# nexus5.net
KiCad netlist of a schematic drawn in Altium Designer
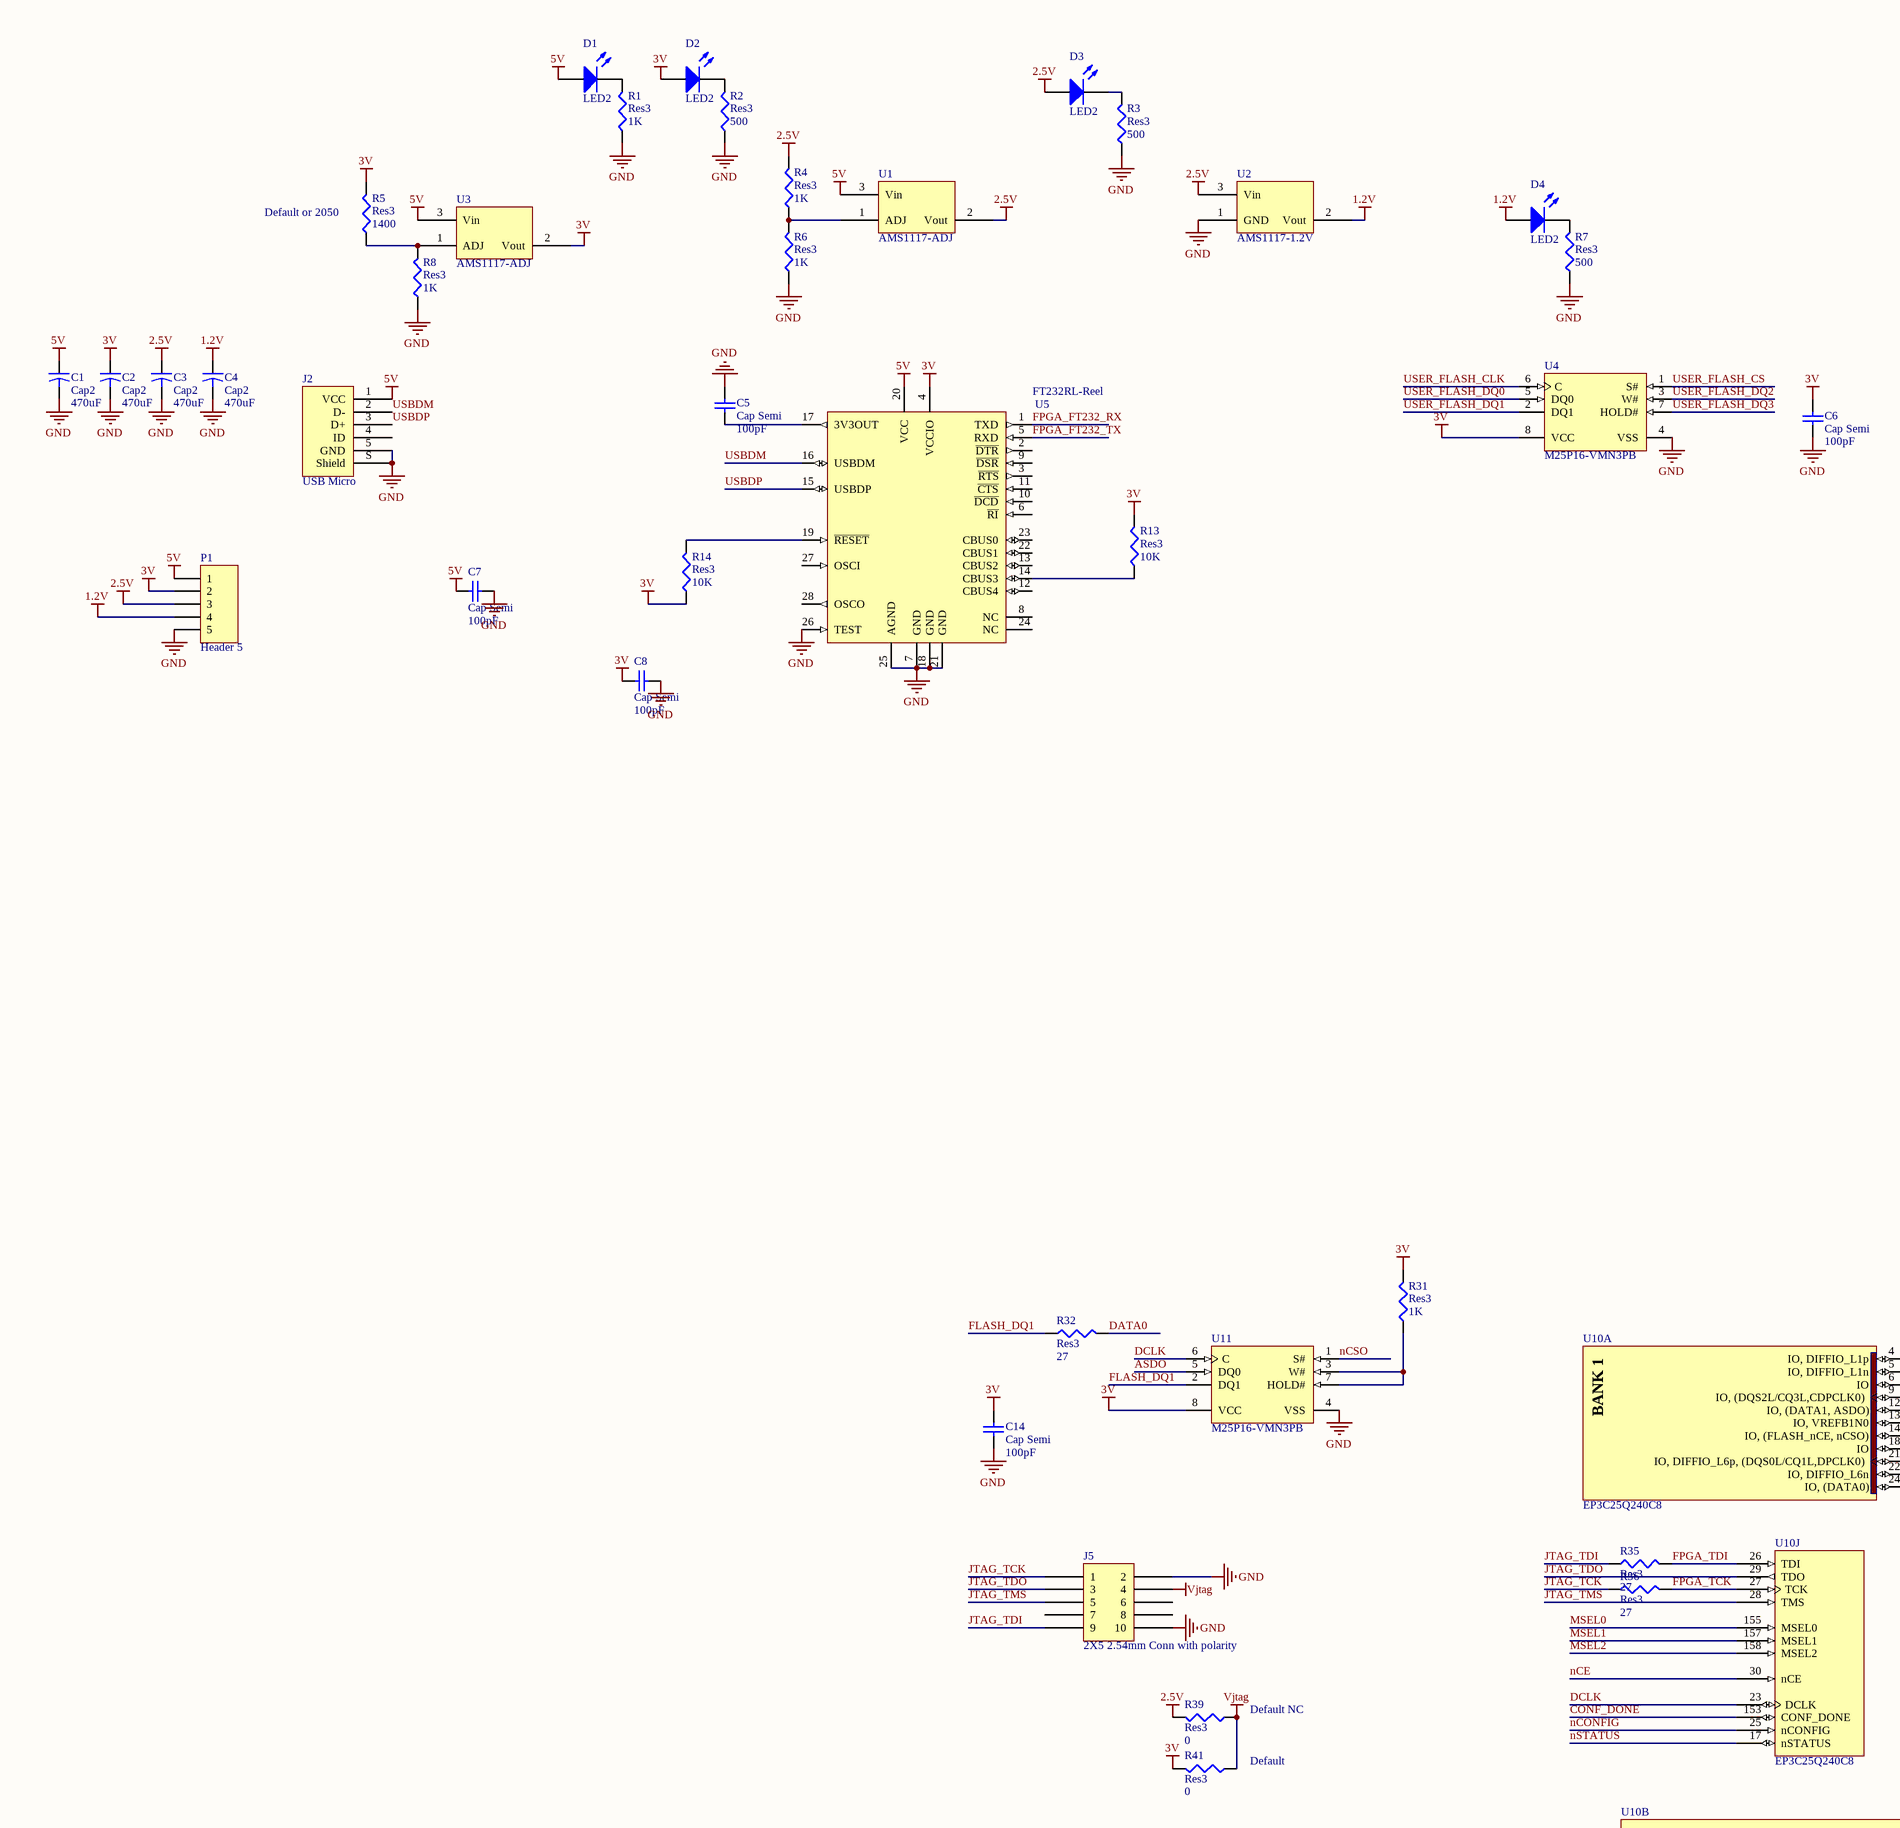
[diagram p0: nexus5.SchDoc, top left]
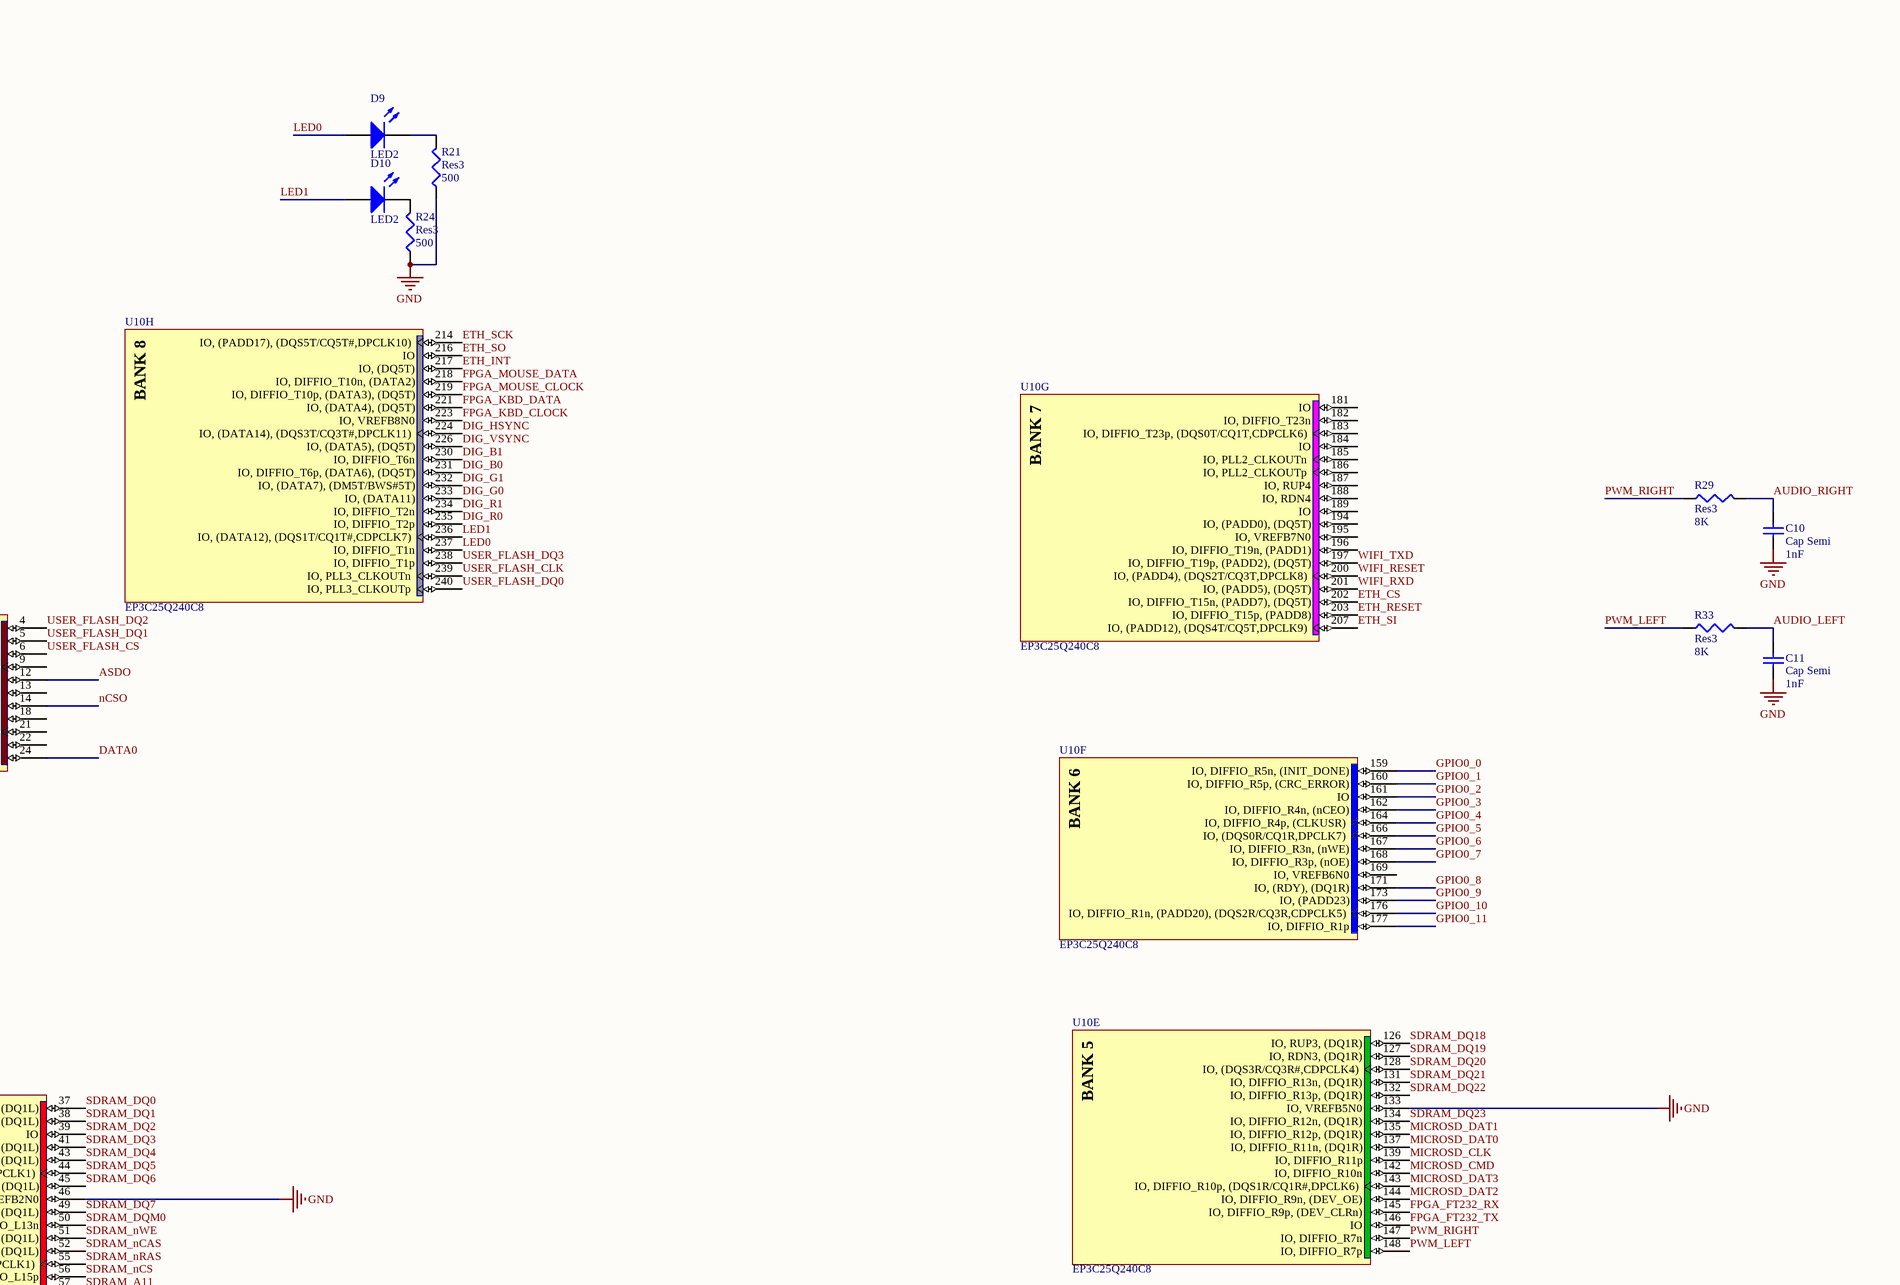
[diagram p1: nexus5.SchDoc, top middle]
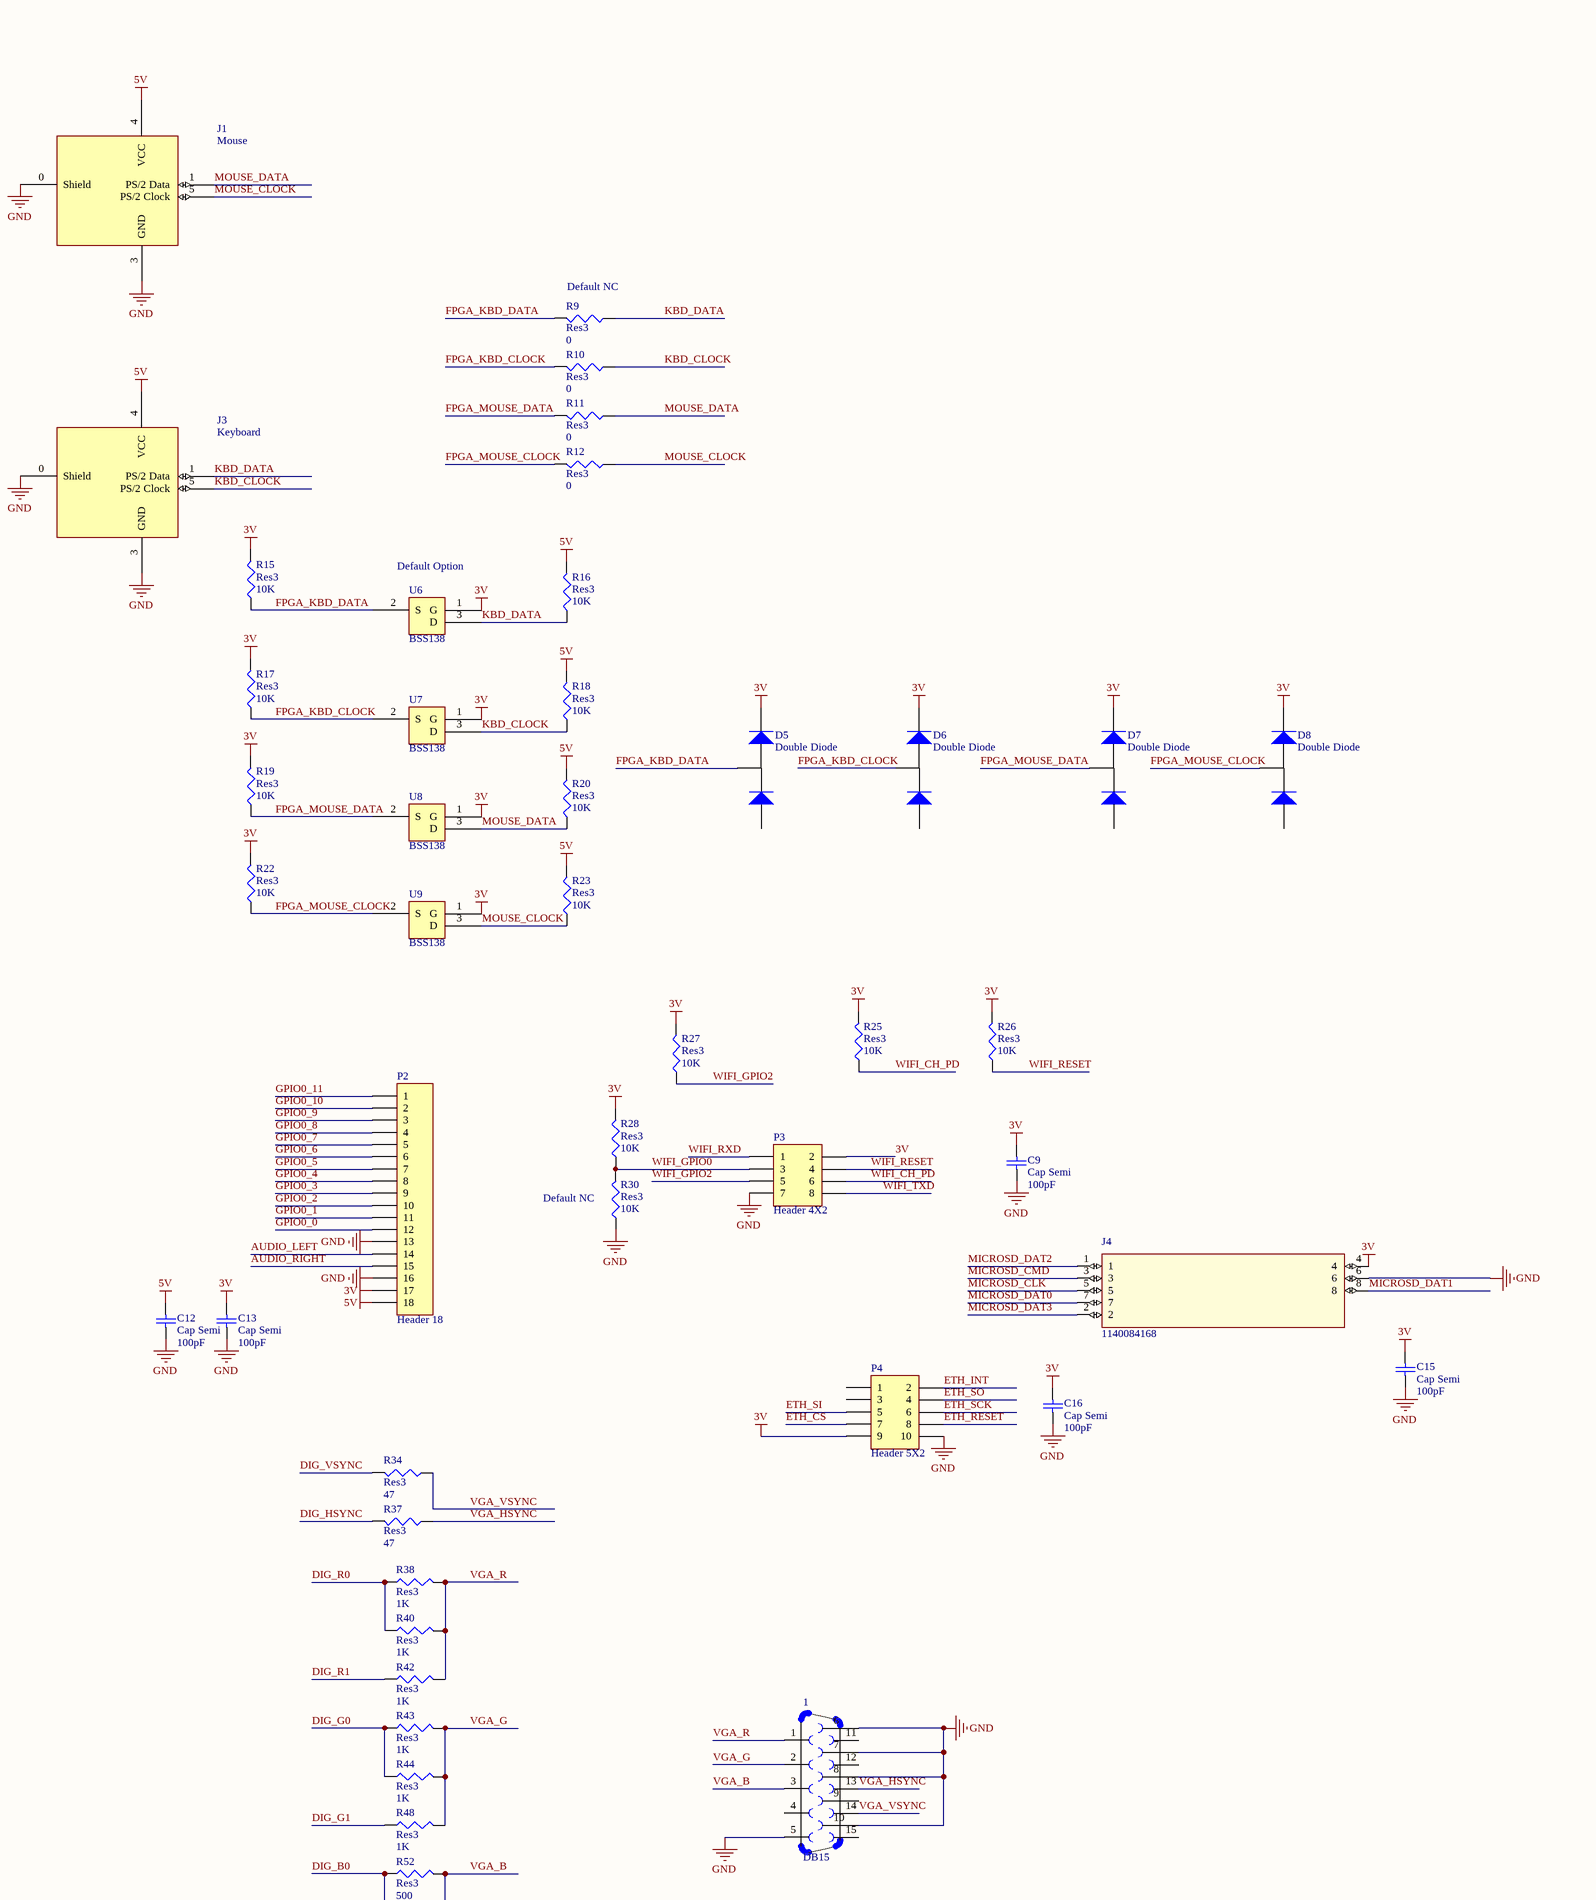
[diagram p2: nexus5.SchDoc, top right]
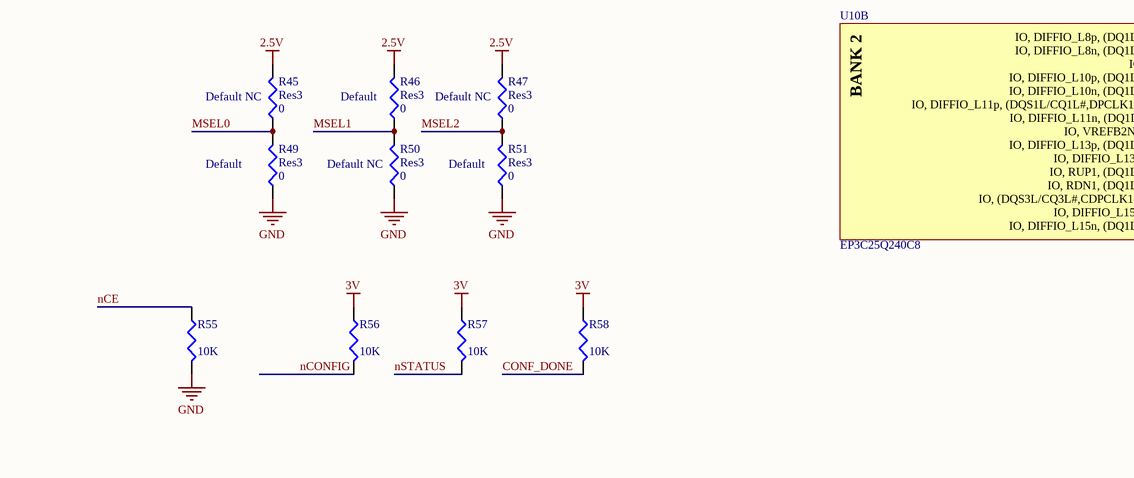
[diagram p3: nexus5.SchDoc, bottom left]
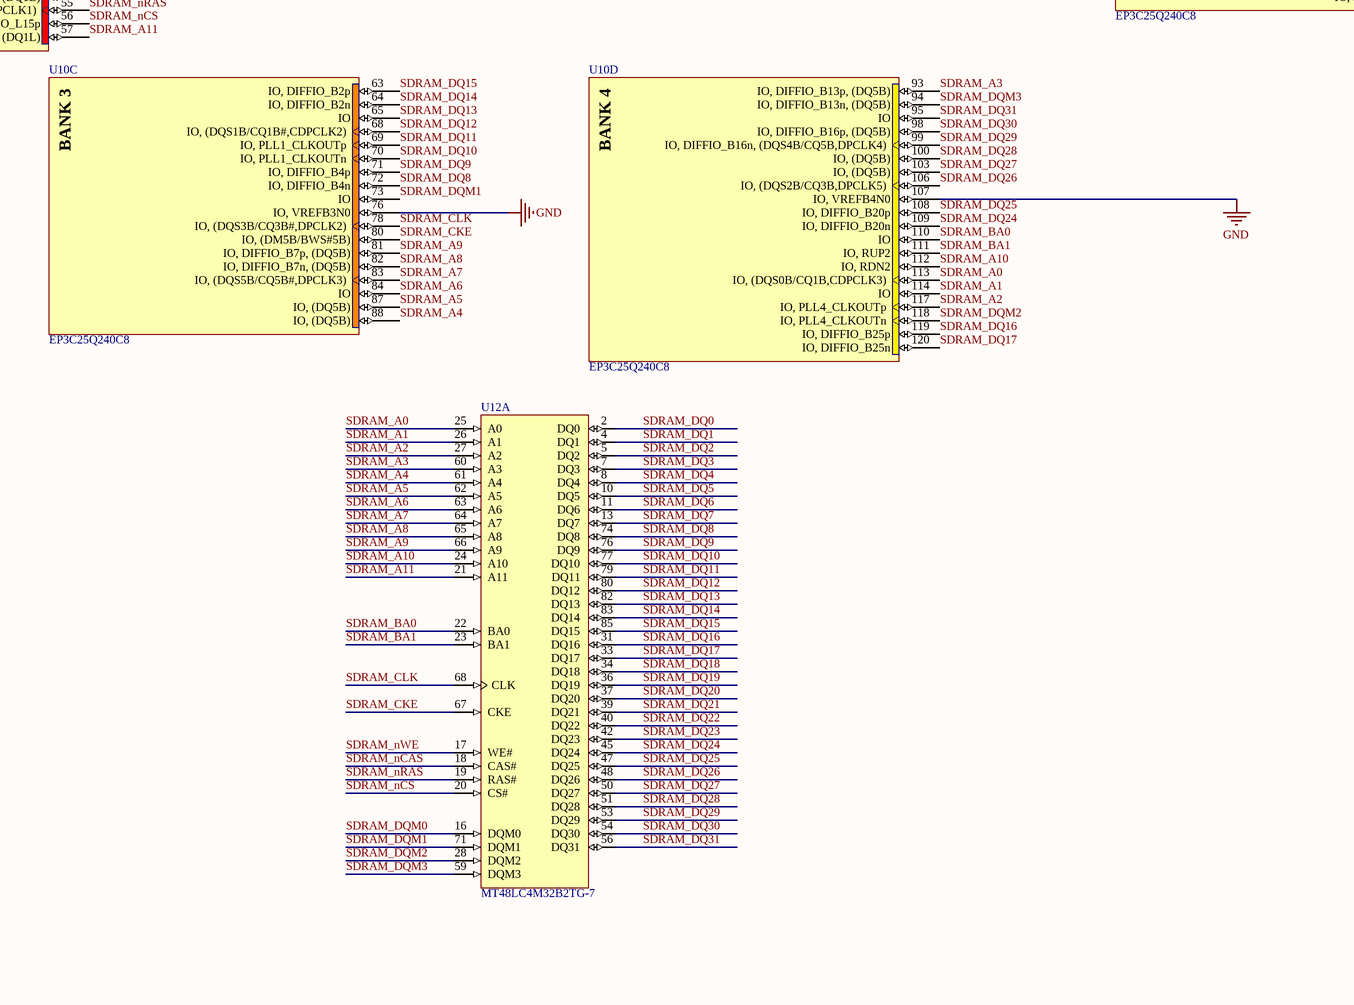
[diagram p4: nexus5.SchDoc, bottom middle]
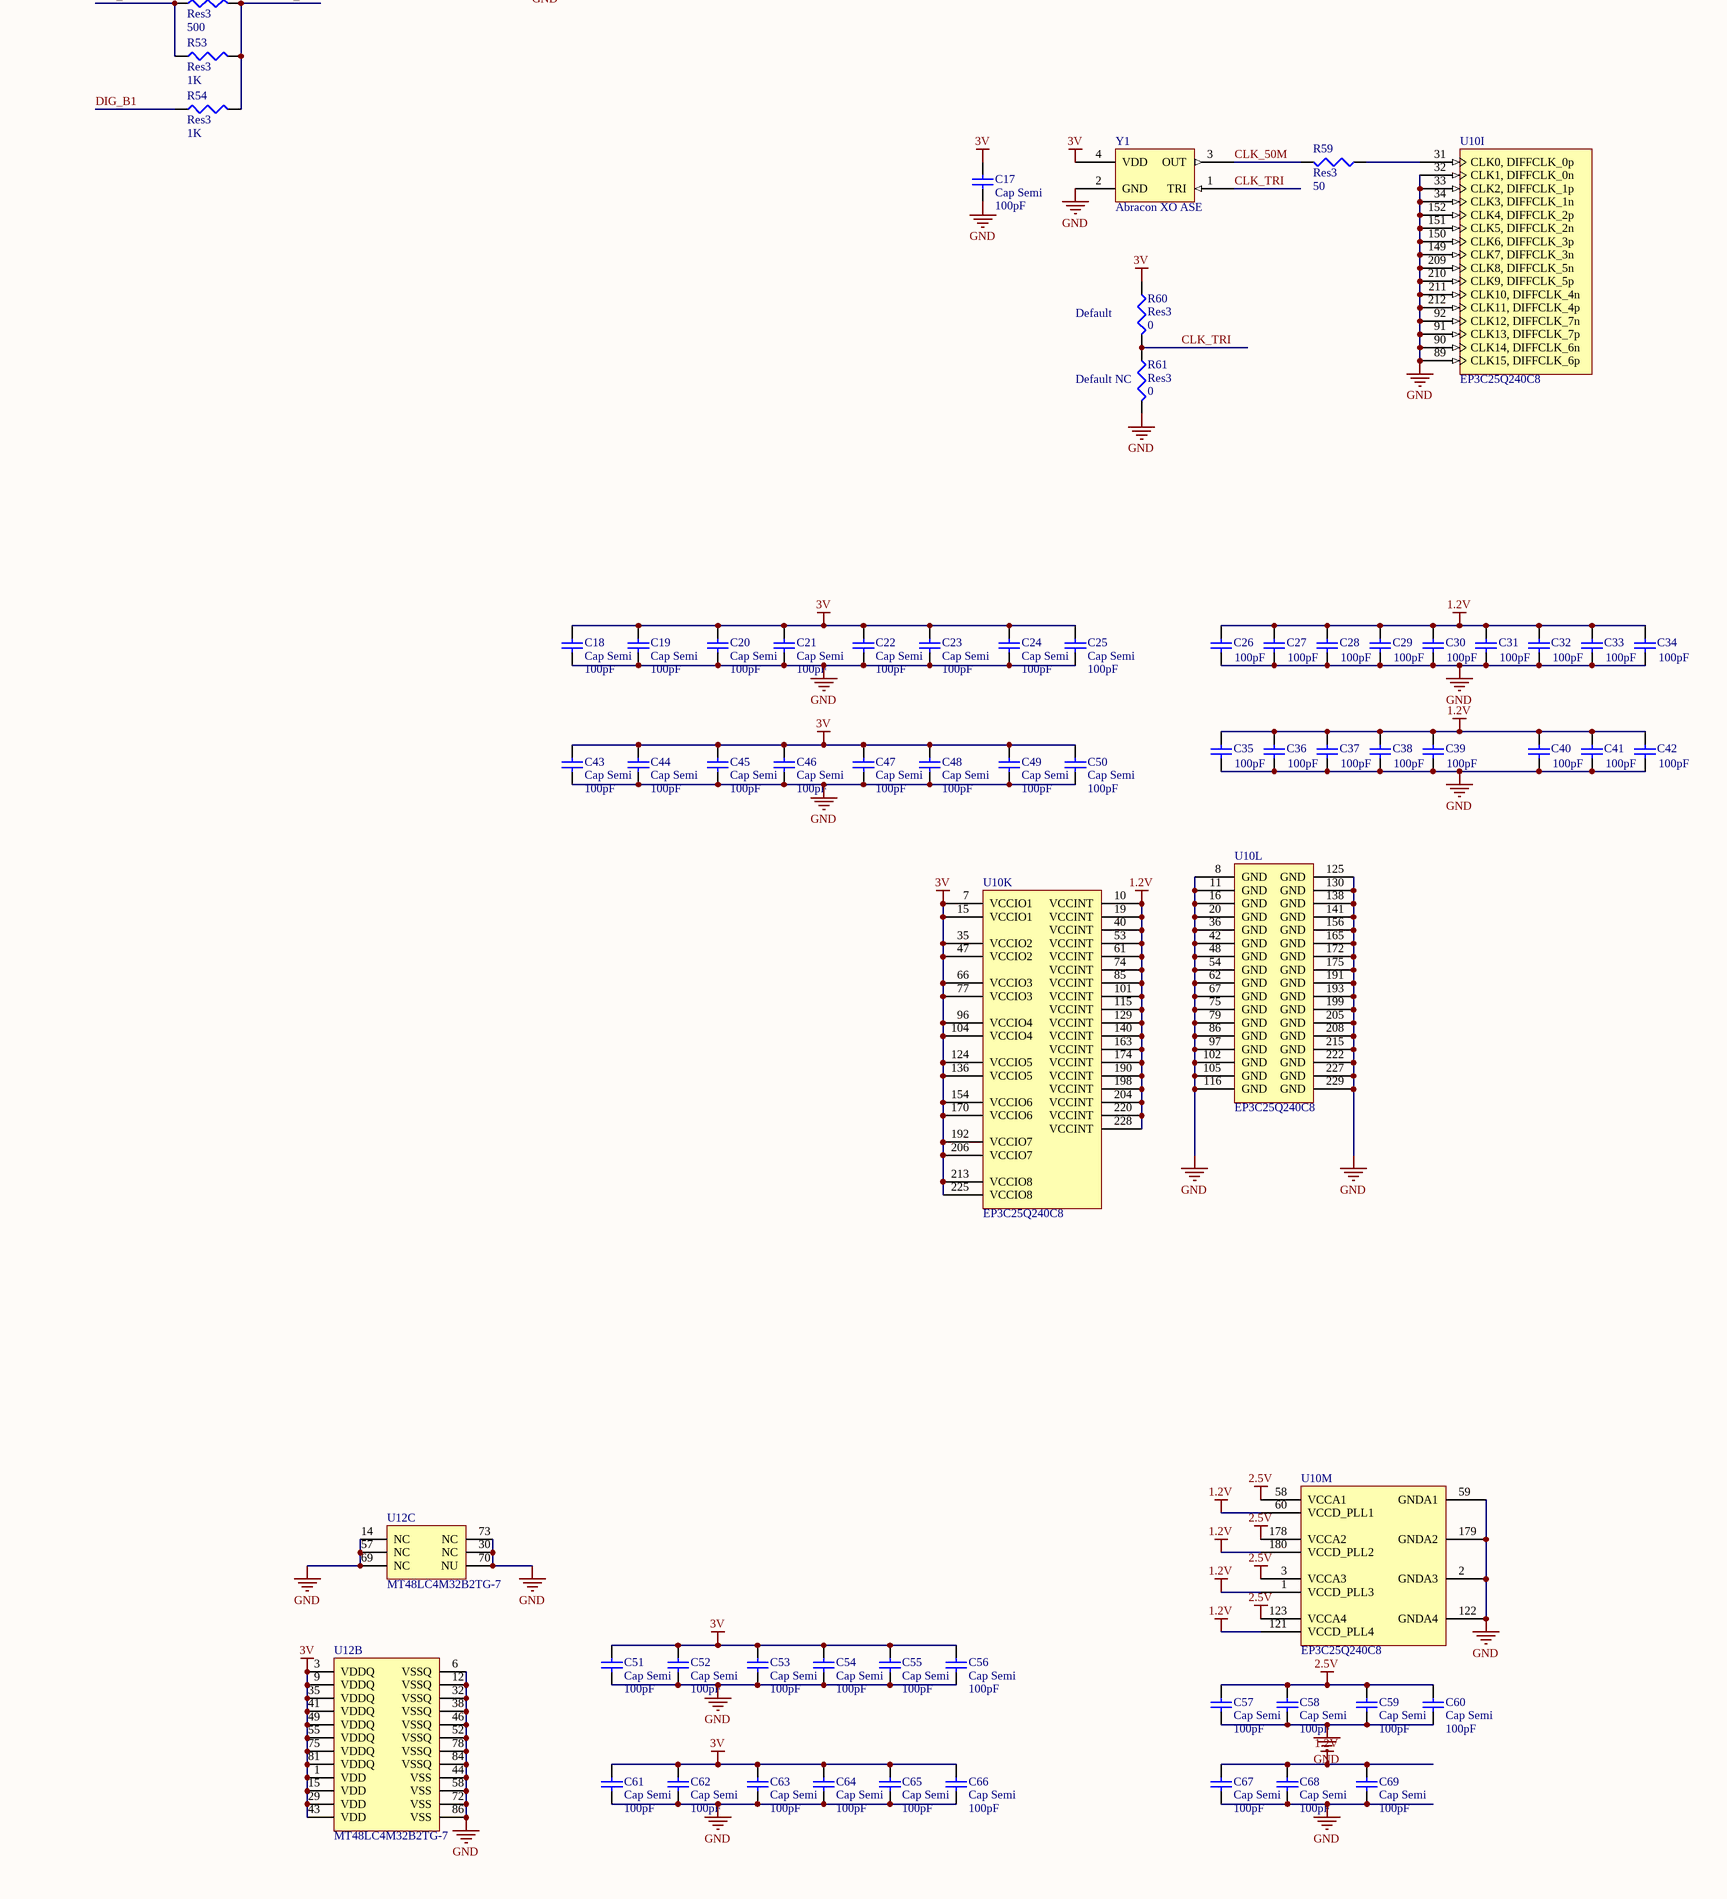
[diagram p5: nexus5.SchDoc, bottom right]

(export (version "E")
  (design (tool "Eeschema 10.0.6"))
  (components
    (comp (ref "1")
      (value "DB15")
      (footprint "*DB15")
      (description "Conn, f, 15rgb, 1 Piece")
      (fields (field (name "MF") "Belden Inc."))
      (libsource (lib "DB15") (part "DB15"))
    )
    (comp (ref "C1")
      (value "Cap2")
      (footprint "Small Cap Pol")
      (description "Capacitor")
      (fields (field (name "ALTIUM_VALUE") "470uF") (field (name "PUBLISHER") "Altium Limited"))
      (libsource (lib "Miscellaneous Devices") (part "Cap2"))
    )
    (comp (ref "C2")
      (value "Cap2")
      (footprint "Small Cap Pol")
      (description "Capacitor")
      (fields (field (name "ALTIUM_VALUE") "470uF") (field (name "PUBLISHER") "Altium Limited"))
      (libsource (lib "Miscellaneous Devices") (part "Cap2"))
    )
    (comp (ref "C3")
      (value "Cap2")
      (footprint "Small Cap Pol")
      (description "Capacitor")
      (fields (field (name "ALTIUM_VALUE") "470uF") (field (name "PUBLISHER") "Altium Limited"))
      (libsource (lib "Miscellaneous Devices") (part "Cap2"))
    )
    (comp (ref "C4")
      (value "Cap2")
      (footprint "Small Cap Pol")
      (description "Capacitor")
      (fields (field (name "ALTIUM_VALUE") "470uF") (field (name "PUBLISHER") "Altium Limited"))
      (libsource (lib "Miscellaneous Devices") (part "Cap2"))
    )
    (comp (ref "C5")
      (value "Cap Semi")
      (footprint "1608[0603]")
      (description "Capacitor (Semiconductor SIM Model)")
      (fields (field (name "ALTIUM_VALUE") "100pF") (field (name "PUBLISHER") "Altium Limited"))
      (libsource (lib "Miscellaneous Devices") (part "Cap Semi"))
    )
    (comp (ref "C6")
      (value "Cap Semi")
      (footprint "1608[0603]")
      (description "Capacitor (Semiconductor SIM Model)")
      (fields (field (name "ALTIUM_VALUE") "100pF") (field (name "PUBLISHER") "Altium Limited"))
      (libsource (lib "Miscellaneous Devices") (part "Cap Semi"))
    )
    (comp (ref "C7")
      (value "Cap Semi")
      (footprint "1608[0603]")
      (description "Capacitor (Semiconductor SIM Model)")
      (fields (field (name "ALTIUM_VALUE") "100pF") (field (name "PUBLISHER") "Altium Limited"))
      (libsource (lib "Miscellaneous Devices") (part "Cap Semi"))
    )
    (comp (ref "C8")
      (value "Cap Semi")
      (footprint "1608[0603]")
      (description "Capacitor (Semiconductor SIM Model)")
      (fields (field (name "ALTIUM_VALUE") "100pF") (field (name "PUBLISHER") "Altium Limited"))
      (libsource (lib "Miscellaneous Devices") (part "Cap Semi"))
    )
    (comp (ref "C9")
      (value "Cap Semi")
      (footprint "1608[0603]")
      (description "Capacitor (Semiconductor SIM Model)")
      (fields (field (name "ALTIUM_VALUE") "100pF") (field (name "PUBLISHER") "Altium Limited"))
      (libsource (lib "Miscellaneous Devices") (part "Cap Semi"))
    )
    (comp (ref "C10")
      (value "Cap Semi")
      (footprint "1608[0603]")
      (description "Capacitor (Semiconductor SIM Model)")
      (fields (field (name "ALTIUM_VALUE") "1nF") (field (name "PUBLISHER") "Altium Limited"))
      (libsource (lib "Miscellaneous Devices") (part "Cap Semi"))
    )
    (comp (ref "C11")
      (value "Cap Semi")
      (footprint "1608[0603]")
      (description "Capacitor (Semiconductor SIM Model)")
      (fields (field (name "ALTIUM_VALUE") "1nF") (field (name "PUBLISHER") "Altium Limited"))
      (libsource (lib "Miscellaneous Devices") (part "Cap Semi"))
    )
    (comp (ref "C12")
      (value "Cap Semi")
      (footprint "1608[0603]")
      (description "Capacitor (Semiconductor SIM Model)")
      (fields (field (name "ALTIUM_VALUE") "100pF") (field (name "PUBLISHER") "Altium Limited"))
      (libsource (lib "Miscellaneous Devices") (part "Cap Semi"))
    )
    (comp (ref "C13")
      (value "Cap Semi")
      (footprint "1608[0603]")
      (description "Capacitor (Semiconductor SIM Model)")
      (fields (field (name "ALTIUM_VALUE") "100pF") (field (name "PUBLISHER") "Altium Limited"))
      (libsource (lib "Miscellaneous Devices") (part "Cap Semi"))
    )
    (comp (ref "C14")
      (value "Cap Semi")
      (footprint "1608[0603]")
      (description "Capacitor (Semiconductor SIM Model)")
      (fields (field (name "ALTIUM_VALUE") "100pF") (field (name "PUBLISHER") "Altium Limited"))
      (libsource (lib "Miscellaneous Devices") (part "Cap Semi"))
    )
    (comp (ref "C15")
      (value "Cap Semi")
      (footprint "1608[0603]")
      (description "Capacitor (Semiconductor SIM Model)")
      (fields (field (name "ALTIUM_VALUE") "100pF") (field (name "PUBLISHER") "Altium Limited"))
      (libsource (lib "Miscellaneous Devices") (part "Cap Semi"))
    )
    (comp (ref "C16")
      (value "Cap Semi")
      (footprint "1608[0603]")
      (description "Capacitor (Semiconductor SIM Model)")
      (fields (field (name "ALTIUM_VALUE") "100pF") (field (name "PUBLISHER") "Altium Limited"))
      (libsource (lib "Miscellaneous Devices") (part "Cap Semi"))
    )
    (comp (ref "C17")
      (value "Cap Semi")
      (footprint "1608[0603]")
      (description "Capacitor (Semiconductor SIM Model)")
      (fields (field (name "ALTIUM_VALUE") "100pF") (field (name "PUBLISHER") "Altium Limited"))
      (libsource (lib "Miscellaneous Devices") (part "Cap Semi"))
    )
    (comp (ref "C18")
      (value "Cap Semi")
      (footprint "1608[0603]")
      (description "Capacitor (Semiconductor SIM Model)")
      (fields (field (name "ALTIUM_VALUE") "100pF") (field (name "PUBLISHER") "Altium Limited"))
      (libsource (lib "Miscellaneous Devices") (part "Cap Semi"))
    )
    (comp (ref "C19")
      (value "Cap Semi")
      (footprint "1608[0603]")
      (description "Capacitor (Semiconductor SIM Model)")
      (fields (field (name "ALTIUM_VALUE") "100pF") (field (name "PUBLISHER") "Altium Limited"))
      (libsource (lib "Miscellaneous Devices") (part "Cap Semi"))
    )
    (comp (ref "C20")
      (value "Cap Semi")
      (footprint "1608[0603]")
      (description "Capacitor (Semiconductor SIM Model)")
      (fields (field (name "ALTIUM_VALUE") "100pF") (field (name "PUBLISHER") "Altium Limited"))
      (libsource (lib "Miscellaneous Devices") (part "Cap Semi"))
    )
    (comp (ref "C21")
      (value "Cap Semi")
      (footprint "1608[0603]")
      (description "Capacitor (Semiconductor SIM Model)")
      (fields (field (name "ALTIUM_VALUE") "100pF") (field (name "PUBLISHER") "Altium Limited"))
      (libsource (lib "Miscellaneous Devices") (part "Cap Semi"))
    )
    (comp (ref "C22")
      (value "Cap Semi")
      (footprint "1608[0603]")
      (description "Capacitor (Semiconductor SIM Model)")
      (fields (field (name "ALTIUM_VALUE") "100pF") (field (name "PUBLISHER") "Altium Limited"))
      (libsource (lib "Miscellaneous Devices") (part "Cap Semi"))
    )
    (comp (ref "C23")
      (value "Cap Semi")
      (footprint "1608[0603]")
      (description "Capacitor (Semiconductor SIM Model)")
      (fields (field (name "ALTIUM_VALUE") "100pF") (field (name "PUBLISHER") "Altium Limited"))
      (libsource (lib "Miscellaneous Devices") (part "Cap Semi"))
    )
    (comp (ref "C24")
      (value "Cap Semi")
      (footprint "1608[0603]")
      (description "Capacitor (Semiconductor SIM Model)")
      (fields (field (name "ALTIUM_VALUE") "100pF") (field (name "PUBLISHER") "Altium Limited"))
      (libsource (lib "Miscellaneous Devices") (part "Cap Semi"))
    )
    (comp (ref "C25")
      (value "Cap Semi")
      (footprint "1608[0603]")
      (description "Capacitor (Semiconductor SIM Model)")
      (fields (field (name "ALTIUM_VALUE") "100pF") (field (name "PUBLISHER") "Altium Limited"))
      (libsource (lib "Miscellaneous Devices") (part "Cap Semi"))
    )
    (comp (ref "C26")
      (value "100pF")
      (footprint "1608[0603]")
      (description "Capacitor (Semiconductor SIM Model)")
      (fields (field (name "Comment") "Cap Semi") (field (name "PUBLISHER") "Altium Limited"))
      (libsource (lib "Miscellaneous Devices") (part "Cap Semi"))
    )
    (comp (ref "C27")
      (value "100pF")
      (footprint "1608[0603]")
      (description "Capacitor (Semiconductor SIM Model)")
      (fields (field (name "Comment") "Cap Semi") (field (name "PUBLISHER") "Altium Limited"))
      (libsource (lib "Miscellaneous Devices") (part "Cap Semi"))
    )
    (comp (ref "C28")
      (value "100pF")
      (footprint "1608[0603]")
      (description "Capacitor (Semiconductor SIM Model)")
      (fields (field (name "Comment") "Cap Semi") (field (name "PUBLISHER") "Altium Limited"))
      (libsource (lib "Miscellaneous Devices") (part "Cap Semi"))
    )
    (comp (ref "C29")
      (value "100pF")
      (footprint "1608[0603]")
      (description "Capacitor (Semiconductor SIM Model)")
      (fields (field (name "Comment") "Cap Semi") (field (name "PUBLISHER") "Altium Limited"))
      (libsource (lib "Miscellaneous Devices") (part "Cap Semi"))
    )
    (comp (ref "C30")
      (value "100pF")
      (footprint "1608[0603]")
      (description "Capacitor (Semiconductor SIM Model)")
      (fields (field (name "Comment") "Cap Semi") (field (name "PUBLISHER") "Altium Limited"))
      (libsource (lib "Miscellaneous Devices") (part "Cap Semi"))
    )
    (comp (ref "C31")
      (value "100pF")
      (footprint "1608[0603]")
      (description "Capacitor (Semiconductor SIM Model)")
      (fields (field (name "Comment") "Cap Semi") (field (name "PUBLISHER") "Altium Limited"))
      (libsource (lib "Miscellaneous Devices") (part "Cap Semi"))
    )
    (comp (ref "C32")
      (value "100pF")
      (footprint "1608[0603]")
      (description "Capacitor (Semiconductor SIM Model)")
      (fields (field (name "Comment") "Cap Semi") (field (name "PUBLISHER") "Altium Limited"))
      (libsource (lib "Miscellaneous Devices") (part "Cap Semi"))
    )
    (comp (ref "C33")
      (value "100pF")
      (footprint "1608[0603]")
      (description "Capacitor (Semiconductor SIM Model)")
      (fields (field (name "Comment") "Cap Semi") (field (name "PUBLISHER") "Altium Limited"))
      (libsource (lib "Miscellaneous Devices") (part "Cap Semi"))
    )
    (comp (ref "C34")
      (value "100pF")
      (footprint "1608[0603]")
      (description "Capacitor (Semiconductor SIM Model)")
      (fields (field (name "Comment") "Cap Semi") (field (name "PUBLISHER") "Altium Limited"))
      (libsource (lib "Miscellaneous Devices") (part "Cap Semi"))
    )
    (comp (ref "C35")
      (value "100pF")
      (footprint "1608[0603]")
      (description "Capacitor (Semiconductor SIM Model)")
      (fields (field (name "Comment") "Cap Semi") (field (name "PUBLISHER") "Altium Limited"))
      (libsource (lib "Miscellaneous Devices") (part "Cap Semi"))
    )
    (comp (ref "C36")
      (value "100pF")
      (footprint "1608[0603]")
      (description "Capacitor (Semiconductor SIM Model)")
      (fields (field (name "Comment") "Cap Semi") (field (name "PUBLISHER") "Altium Limited"))
      (libsource (lib "Miscellaneous Devices") (part "Cap Semi"))
    )
    (comp (ref "C37")
      (value "100pF")
      (footprint "1608[0603]")
      (description "Capacitor (Semiconductor SIM Model)")
      (fields (field (name "Comment") "Cap Semi") (field (name "PUBLISHER") "Altium Limited"))
      (libsource (lib "Miscellaneous Devices") (part "Cap Semi"))
    )
    (comp (ref "C38")
      (value "100pF")
      (footprint "1608[0603]")
      (description "Capacitor (Semiconductor SIM Model)")
      (fields (field (name "Comment") "Cap Semi") (field (name "PUBLISHER") "Altium Limited"))
      (libsource (lib "Miscellaneous Devices") (part "Cap Semi"))
    )
    (comp (ref "C39")
      (value "100pF")
      (footprint "1608[0603]")
      (description "Capacitor (Semiconductor SIM Model)")
      (fields (field (name "Comment") "Cap Semi") (field (name "PUBLISHER") "Altium Limited"))
      (libsource (lib "Miscellaneous Devices") (part "Cap Semi"))
    )
    (comp (ref "C40")
      (value "100pF")
      (footprint "1608[0603]")
      (description "Capacitor (Semiconductor SIM Model)")
      (fields (field (name "Comment") "Cap Semi") (field (name "PUBLISHER") "Altium Limited"))
      (libsource (lib "Miscellaneous Devices") (part "Cap Semi"))
    )
    (comp (ref "C41")
      (value "100pF")
      (footprint "1608[0603]")
      (description "Capacitor (Semiconductor SIM Model)")
      (fields (field (name "Comment") "Cap Semi") (field (name "PUBLISHER") "Altium Limited"))
      (libsource (lib "Miscellaneous Devices") (part "Cap Semi"))
    )
    (comp (ref "C42")
      (value "100pF")
      (footprint "1608[0603]")
      (description "Capacitor (Semiconductor SIM Model)")
      (fields (field (name "Comment") "Cap Semi") (field (name "PUBLISHER") "Altium Limited"))
      (libsource (lib "Miscellaneous Devices") (part "Cap Semi"))
    )
    (comp (ref "C43")
      (value "Cap Semi")
      (footprint "1608[0603]")
      (description "Capacitor (Semiconductor SIM Model)")
      (fields (field (name "ALTIUM_VALUE") "100pF") (field (name "PUBLISHER") "Altium Limited"))
      (libsource (lib "Miscellaneous Devices") (part "Cap Semi"))
    )
    (comp (ref "C44")
      (value "Cap Semi")
      (footprint "1608[0603]")
      (description "Capacitor (Semiconductor SIM Model)")
      (fields (field (name "ALTIUM_VALUE") "100pF") (field (name "PUBLISHER") "Altium Limited"))
      (libsource (lib "Miscellaneous Devices") (part "Cap Semi"))
    )
    (comp (ref "C45")
      (value "Cap Semi")
      (footprint "1608[0603]")
      (description "Capacitor (Semiconductor SIM Model)")
      (fields (field (name "ALTIUM_VALUE") "100pF") (field (name "PUBLISHER") "Altium Limited"))
      (libsource (lib "Miscellaneous Devices") (part "Cap Semi"))
    )
    (comp (ref "C46")
      (value "Cap Semi")
      (footprint "1608[0603]")
      (description "Capacitor (Semiconductor SIM Model)")
      (fields (field (name "ALTIUM_VALUE") "100pF") (field (name "PUBLISHER") "Altium Limited"))
      (libsource (lib "Miscellaneous Devices") (part "Cap Semi"))
    )
    (comp (ref "C47")
      (value "Cap Semi")
      (footprint "1608[0603]")
      (description "Capacitor (Semiconductor SIM Model)")
      (fields (field (name "ALTIUM_VALUE") "100pF") (field (name "PUBLISHER") "Altium Limited"))
      (libsource (lib "Miscellaneous Devices") (part "Cap Semi"))
    )
    (comp (ref "C48")
      (value "Cap Semi")
      (footprint "1608[0603]")
      (description "Capacitor (Semiconductor SIM Model)")
      (fields (field (name "ALTIUM_VALUE") "100pF") (field (name "PUBLISHER") "Altium Limited"))
      (libsource (lib "Miscellaneous Devices") (part "Cap Semi"))
    )
    (comp (ref "C49")
      (value "Cap Semi")
      (footprint "1608[0603]")
      (description "Capacitor (Semiconductor SIM Model)")
      (fields (field (name "ALTIUM_VALUE") "100pF") (field (name "PUBLISHER") "Altium Limited"))
      (libsource (lib "Miscellaneous Devices") (part "Cap Semi"))
    )
    (comp (ref "C50")
      (value "Cap Semi")
      (footprint "1608[0603]")
      (description "Capacitor (Semiconductor SIM Model)")
      (fields (field (name "ALTIUM_VALUE") "100pF") (field (name "PUBLISHER") "Altium Limited"))
      (libsource (lib "Miscellaneous Devices") (part "Cap Semi"))
    )
    (comp (ref "C51")
      (value "Cap Semi")
      (footprint "1608[0603]")
      (description "Capacitor (Semiconductor SIM Model)")
      (fields (field (name "ALTIUM_VALUE") "100pF") (field (name "PUBLISHER") "Altium Limited"))
      (libsource (lib "Miscellaneous Devices") (part "Cap Semi"))
    )
    (comp (ref "C52")
      (value "Cap Semi")
      (footprint "1608[0603]")
      (description "Capacitor (Semiconductor SIM Model)")
      (fields (field (name "ALTIUM_VALUE") "100pF") (field (name "PUBLISHER") "Altium Limited"))
      (libsource (lib "Miscellaneous Devices") (part "Cap Semi"))
    )
    (comp (ref "C53")
      (value "Cap Semi")
      (footprint "1608[0603]")
      (description "Capacitor (Semiconductor SIM Model)")
      (fields (field (name "ALTIUM_VALUE") "100pF") (field (name "PUBLISHER") "Altium Limited"))
      (libsource (lib "Miscellaneous Devices") (part "Cap Semi"))
    )
    (comp (ref "C54")
      (value "Cap Semi")
      (footprint "1608[0603]")
      (description "Capacitor (Semiconductor SIM Model)")
      (fields (field (name "ALTIUM_VALUE") "100pF") (field (name "PUBLISHER") "Altium Limited"))
      (libsource (lib "Miscellaneous Devices") (part "Cap Semi"))
    )
    (comp (ref "C55")
      (value "Cap Semi")
      (footprint "1608[0603]")
      (description "Capacitor (Semiconductor SIM Model)")
      (fields (field (name "ALTIUM_VALUE") "100pF") (field (name "PUBLISHER") "Altium Limited"))
      (libsource (lib "Miscellaneous Devices") (part "Cap Semi"))
    )
    (comp (ref "C56")
      (value "Cap Semi")
      (footprint "1608[0603]")
      (description "Capacitor (Semiconductor SIM Model)")
      (fields (field (name "ALTIUM_VALUE") "100pF") (field (name "PUBLISHER") "Altium Limited"))
      (libsource (lib "Miscellaneous Devices") (part "Cap Semi"))
    )
    (comp (ref "C57")
      (value "Cap Semi")
      (footprint "1608[0603]")
      (description "Capacitor (Semiconductor SIM Model)")
      (fields (field (name "ALTIUM_VALUE") "100pF") (field (name "PUBLISHER") "Altium Limited"))
      (libsource (lib "Miscellaneous Devices") (part "Cap Semi"))
    )
    (comp (ref "C58")
      (value "Cap Semi")
      (footprint "1608[0603]")
      (description "Capacitor (Semiconductor SIM Model)")
      (fields (field (name "ALTIUM_VALUE") "100pF") (field (name "PUBLISHER") "Altium Limited"))
      (libsource (lib "Miscellaneous Devices") (part "Cap Semi"))
    )
    (comp (ref "C59")
      (value "Cap Semi")
      (footprint "1608[0603]")
      (description "Capacitor (Semiconductor SIM Model)")
      (fields (field (name "ALTIUM_VALUE") "100pF") (field (name "PUBLISHER") "Altium Limited"))
      (libsource (lib "Miscellaneous Devices") (part "Cap Semi"))
    )
    (comp (ref "C60")
      (value "Cap Semi")
      (footprint "1608[0603]")
      (description "Capacitor (Semiconductor SIM Model)")
      (fields (field (name "ALTIUM_VALUE") "100pF") (field (name "PUBLISHER") "Altium Limited"))
      (libsource (lib "Miscellaneous Devices") (part "Cap Semi"))
    )
    (comp (ref "C61")
      (value "Cap Semi")
      (footprint "1608[0603]")
      (description "Capacitor (Semiconductor SIM Model)")
      (fields (field (name "ALTIUM_VALUE") "100pF") (field (name "PUBLISHER") "Altium Limited"))
      (libsource (lib "Miscellaneous Devices") (part "Cap Semi"))
    )
    (comp (ref "C62")
      (value "Cap Semi")
      (footprint "1608[0603]")
      (description "Capacitor (Semiconductor SIM Model)")
      (fields (field (name "ALTIUM_VALUE") "100pF") (field (name "PUBLISHER") "Altium Limited"))
      (libsource (lib "Miscellaneous Devices") (part "Cap Semi"))
    )
    (comp (ref "C63")
      (value "Cap Semi")
      (footprint "1608[0603]")
      (description "Capacitor (Semiconductor SIM Model)")
      (fields (field (name "ALTIUM_VALUE") "100pF") (field (name "PUBLISHER") "Altium Limited"))
      (libsource (lib "Miscellaneous Devices") (part "Cap Semi"))
    )
    (comp (ref "C64")
      (value "Cap Semi")
      (footprint "1608[0603]")
      (description "Capacitor (Semiconductor SIM Model)")
      (fields (field (name "ALTIUM_VALUE") "100pF") (field (name "PUBLISHER") "Altium Limited"))
      (libsource (lib "Miscellaneous Devices") (part "Cap Semi"))
    )
    (comp (ref "C65")
      (value "Cap Semi")
      (footprint "1608[0603]")
      (description "Capacitor (Semiconductor SIM Model)")
      (fields (field (name "ALTIUM_VALUE") "100pF") (field (name "PUBLISHER") "Altium Limited"))
      (libsource (lib "Miscellaneous Devices") (part "Cap Semi"))
    )
    (comp (ref "C66")
      (value "Cap Semi")
      (footprint "1608[0603]")
      (description "Capacitor (Semiconductor SIM Model)")
      (fields (field (name "ALTIUM_VALUE") "100pF") (field (name "PUBLISHER") "Altium Limited"))
      (libsource (lib "Miscellaneous Devices") (part "Cap Semi"))
    )
    (comp (ref "C67")
      (value "Cap Semi")
      (footprint "1608[0603]")
      (description "Capacitor (Semiconductor SIM Model)")
      (fields (field (name "ALTIUM_VALUE") "100pF") (field (name "PUBLISHER") "Altium Limited"))
      (libsource (lib "Miscellaneous Devices") (part "Cap Semi"))
    )
    (comp (ref "C68")
      (value "Cap Semi")
      (footprint "1608[0603]")
      (description "Capacitor (Semiconductor SIM Model)")
      (fields (field (name "ALTIUM_VALUE") "100pF") (field (name "PUBLISHER") "Altium Limited"))
      (libsource (lib "Miscellaneous Devices") (part "Cap Semi"))
    )
    (comp (ref "C69")
      (value "Cap Semi")
      (footprint "1608[0603]")
      (description "Capacitor (Semiconductor SIM Model)")
      (fields (field (name "ALTIUM_VALUE") "100pF") (field (name "PUBLISHER") "Altium Limited"))
      (libsource (lib "Miscellaneous Devices") (part "Cap Semi"))
    )
    (comp (ref "D1")
      (value "LED2")
      (footprint "3.2X1.6X1.1")
      (description "Typical RED, GREEN, YELLOW, AMBER GaAs LED")
      (fields (field (name "PUBLISHER") "Altium Limited"))
      (libsource (lib "Miscellaneous Devices") (part "LED2"))
    )
    (comp (ref "D2")
      (value "LED2")
      (footprint "3.2X1.6X1.1")
      (description "Typical RED, GREEN, YELLOW, AMBER GaAs LED")
      (fields (field (name "PUBLISHER") "Altium Limited"))
      (libsource (lib "Miscellaneous Devices") (part "LED2"))
    )
    (comp (ref "D3")
      (value "LED2")
      (footprint "3.2X1.6X1.1")
      (description "Typical RED, GREEN, YELLOW, AMBER GaAs LED")
      (fields (field (name "PUBLISHER") "Altium Limited"))
      (libsource (lib "Miscellaneous Devices") (part "LED2"))
    )
    (comp (ref "D4")
      (value "LED2")
      (footprint "3.2X1.6X1.1")
      (description "Typical RED, GREEN, YELLOW, AMBER GaAs LED")
      (fields (field (name "PUBLISHER") "Altium Limited"))
      (libsource (lib "Miscellaneous Devices") (part "LED2"))
    )
    (comp (ref "D5") (value "Double Diode") (footprint "SOT-23") (libsource (lib "BAT54S") (part "BAT54S")))
    (comp (ref "D6") (value "Double Diode") (footprint "SOT-23") (libsource (lib "BAT54S") (part "BAT54S")))
    (comp (ref "D7") (value "Double Diode") (footprint "SOT-23") (libsource (lib "BAT54S") (part "BAT54S")))
    (comp (ref "D8") (value "Double Diode") (footprint "SOT-23") (libsource (lib "BAT54S") (part "BAT54S")))
    (comp (ref "D9")
      (value "LED2")
      (footprint "3.2X1.6X1.1")
      (description "Typical RED, GREEN, YELLOW, AMBER GaAs LED")
      (fields (field (name "PUBLISHER") "Altium Limited"))
      (libsource (lib "Miscellaneous Devices") (part "LED2"))
    )
    (comp (ref "D10")
      (value "LED2")
      (footprint "3.2X1.6X1.1")
      (description "Typical RED, GREEN, YELLOW, AMBER GaAs LED")
      (fields (field (name "PUBLISHER") "Altium Limited"))
      (libsource (lib "Miscellaneous Devices") (part "LED2"))
    )
    (comp (ref "J1") (value "Mouse") (footprint "MD-60S") (libsource (lib "PSslash2") (part "MD60S")))
    (comp (ref "J2")
      (value "USB Micro")
      (footprint "FCI USB 10118193-0001LF")
      (libsource (lib "MicroUSB") (part "USB 2.0 Type B Micro"))
    )
    (comp (ref "J3") (value "Keyboard") (footprint "MD-60S") (libsource (lib "PSslash2") (part "MD60S")))
    (comp (ref "J4")
      (value "1140084168")
      (footprint "1140084168")
      (description "Memory Card Connector, Microsd, 8 Position, Full Reel")
      (fields (field (name "DIGI-KEY_PART_NUMBER") "114-00841-68-1-ND") (field (name "MF") "Amphenol ICC"))
      (libsource (lib "1140084168") (part "1140084168"))
    )
    (comp (ref "J5")
      (value "2X5 2.54mm Conn with polarity")
      (footprint "2X5 with polarity")
      (libsource (lib "Corner") (part "2X5 2.54mm Conn with polarity"))
    )
    (comp (ref "P1")
      (value "Header 5")
      (footprint "HDR1X5")
      (description "Header, 5-Pin")
      (fields (field (name "PUBLISHER") "Altium Limited"))
      (libsource (lib "Miscellaneous Connectors") (part "Header 5"))
    )
    (comp (ref "P2")
      (value "Header 18")
      (footprint "HDR1X18")
      (description "Header, 18-Pin")
      (fields (field (name "PUBLISHER") "Altium Limited"))
      (libsource (lib "Miscellaneous Connectors") (part "Header 18"))
    )
    (comp (ref "P3")
      (value "Header 4X2")
      (footprint "HDR2X4")
      (description "Header, 4-Pin, Dual row")
      (fields (field (name "PUBLISHER") "Altium Limited"))
      (libsource (lib "Miscellaneous Connectors") (part "Header 4X2"))
    )
    (comp (ref "P4")
      (value "Header 5X2")
      (footprint "HDR2X5")
      (description "Header, 5-Pin, Dual row")
      (fields (field (name "PUBLISHER") "Altium Limited"))
      (libsource (lib "Miscellaneous Connectors") (part "Header 5X2"))
    )
    (comp (ref "R1")
      (value "Res3")
      (footprint "J1-0603")
      (description "Resistor")
      (fields (field (name "ALTIUM_VALUE") "1K") (field (name "PUBLISHER") "Altium Limited"))
      (libsource (lib "Miscellaneous Devices") (part "Res3"))
    )
    (comp (ref "R2")
      (value "Res3")
      (footprint "J1-0603")
      (description "Resistor")
      (fields (field (name "ALTIUM_VALUE") "500") (field (name "PUBLISHER") "Altium Limited"))
      (libsource (lib "Miscellaneous Devices") (part "Res3"))
    )
    (comp (ref "R3")
      (value "Res3")
      (footprint "J1-0603")
      (description "Resistor")
      (fields (field (name "ALTIUM_VALUE") "500") (field (name "PUBLISHER") "Altium Limited"))
      (libsource (lib "Miscellaneous Devices") (part "Res3"))
    )
    (comp (ref "R4")
      (value "Res3")
      (footprint "J1-0603")
      (description "Resistor")
      (fields (field (name "ALTIUM_VALUE") "1K") (field (name "PUBLISHER") "Altium Limited"))
      (libsource (lib "Miscellaneous Devices") (part "Res3"))
    )
    (comp (ref "R5")
      (value "Res3")
      (footprint "J1-0603")
      (description "Resistor")
      (fields (field (name "ALTIUM_VALUE") "1400") (field (name "PUBLISHER") "Altium Limited"))
      (libsource (lib "Miscellaneous Devices") (part "Res3"))
    )
    (comp (ref "R6")
      (value "Res3")
      (footprint "J1-0603")
      (description "Resistor")
      (fields (field (name "ALTIUM_VALUE") "1K") (field (name "PUBLISHER") "Altium Limited"))
      (libsource (lib "Miscellaneous Devices") (part "Res3"))
    )
    (comp (ref "R7")
      (value "Res3")
      (footprint "J1-0603")
      (description "Resistor")
      (fields (field (name "ALTIUM_VALUE") "500") (field (name "PUBLISHER") "Altium Limited"))
      (libsource (lib "Miscellaneous Devices") (part "Res3"))
    )
    (comp (ref "R8")
      (value "Res3")
      (footprint "J1-0603")
      (description "Resistor")
      (fields (field (name "ALTIUM_VALUE") "1K") (field (name "PUBLISHER") "Altium Limited"))
      (libsource (lib "Miscellaneous Devices") (part "Res3"))
    )
    (comp (ref "R9")
      (value "Res3")
      (footprint "J1-0603")
      (description "Resistor")
      (fields (field (name "ALTIUM_VALUE") "0") (field (name "PUBLISHER") "Altium Limited"))
      (libsource (lib "Miscellaneous Devices") (part "Res3"))
    )
    (comp (ref "R10")
      (value "Res3")
      (footprint "J1-0603")
      (description "Resistor")
      (fields (field (name "ALTIUM_VALUE") "0") (field (name "PUBLISHER") "Altium Limited"))
      (libsource (lib "Miscellaneous Devices") (part "Res3"))
    )
    (comp (ref "R11")
      (value "Res3")
      (footprint "J1-0603")
      (description "Resistor")
      (fields (field (name "ALTIUM_VALUE") "0") (field (name "PUBLISHER") "Altium Limited"))
      (libsource (lib "Miscellaneous Devices") (part "Res3"))
    )
    (comp (ref "R12")
      (value "Res3")
      (footprint "J1-0603")
      (description "Resistor")
      (fields (field (name "ALTIUM_VALUE") "0") (field (name "PUBLISHER") "Altium Limited"))
      (libsource (lib "Miscellaneous Devices") (part "Res3"))
    )
    (comp (ref "R13")
      (value "Res3")
      (footprint "J1-0603")
      (description "Resistor")
      (fields (field (name "ALTIUM_VALUE") "10K") (field (name "PUBLISHER") "Altium Limited"))
      (libsource (lib "Miscellaneous Devices") (part "Res3"))
    )
    (comp (ref "R14")
      (value "Res3")
      (footprint "J1-0603")
      (description "Resistor")
      (fields (field (name "ALTIUM_VALUE") "10K") (field (name "PUBLISHER") "Altium Limited"))
      (libsource (lib "Miscellaneous Devices") (part "Res3"))
    )
    (comp (ref "R15")
      (value "Res3")
      (footprint "J1-0603")
      (description "Resistor")
      (fields (field (name "ALTIUM_VALUE") "10K") (field (name "PUBLISHER") "Altium Limited"))
      (libsource (lib "Miscellaneous Devices") (part "Res3"))
    )
    (comp (ref "R16")
      (value "Res3")
      (footprint "J1-0603")
      (description "Resistor")
      (fields (field (name "ALTIUM_VALUE") "10K") (field (name "PUBLISHER") "Altium Limited"))
      (libsource (lib "Miscellaneous Devices") (part "Res3"))
    )
    (comp (ref "R17")
      (value "Res3")
      (footprint "J1-0603")
      (description "Resistor")
      (fields (field (name "ALTIUM_VALUE") "10K") (field (name "PUBLISHER") "Altium Limited"))
      (libsource (lib "Miscellaneous Devices") (part "Res3"))
    )
    (comp (ref "R18")
      (value "Res3")
      (footprint "J1-0603")
      (description "Resistor")
      (fields (field (name "ALTIUM_VALUE") "10K") (field (name "PUBLISHER") "Altium Limited"))
      (libsource (lib "Miscellaneous Devices") (part "Res3"))
    )
    (comp (ref "R19")
      (value "Res3")
      (footprint "J1-0603")
      (description "Resistor")
      (fields (field (name "ALTIUM_VALUE") "10K") (field (name "PUBLISHER") "Altium Limited"))
      (libsource (lib "Miscellaneous Devices") (part "Res3"))
    )
    (comp (ref "R20")
      (value "Res3")
      (footprint "J1-0603")
      (description "Resistor")
      (fields (field (name "ALTIUM_VALUE") "10K") (field (name "PUBLISHER") "Altium Limited"))
      (libsource (lib "Miscellaneous Devices") (part "Res3"))
    )
    (comp (ref "R21")
      (value "Res3")
      (footprint "J1-0603")
      (description "Resistor")
      (fields (field (name "ALTIUM_VALUE") "500") (field (name "PUBLISHER") "Altium Limited"))
      (libsource (lib "Miscellaneous Devices") (part "Res3"))
    )
    (comp (ref "R22")
      (value "Res3")
      (footprint "J1-0603")
      (description "Resistor")
      (fields (field (name "ALTIUM_VALUE") "10K") (field (name "PUBLISHER") "Altium Limited"))
      (libsource (lib "Miscellaneous Devices") (part "Res3"))
    )
    (comp (ref "R23")
      (value "Res3")
      (footprint "J1-0603")
      (description "Resistor")
      (fields (field (name "ALTIUM_VALUE") "10K") (field (name "PUBLISHER") "Altium Limited"))
      (libsource (lib "Miscellaneous Devices") (part "Res3"))
    )
    (comp (ref "R24")
      (value "Res3")
      (footprint "J1-0603")
      (description "Resistor")
      (fields (field (name "ALTIUM_VALUE") "500") (field (name "PUBLISHER") "Altium Limited"))
      (libsource (lib "Miscellaneous Devices") (part "Res3"))
    )
    (comp (ref "R25")
      (value "Res3")
      (footprint "J1-0603")
      (description "Resistor")
      (fields (field (name "ALTIUM_VALUE") "10K") (field (name "PUBLISHER") "Altium Limited"))
      (libsource (lib "Miscellaneous Devices") (part "Res3"))
    )
    (comp (ref "R26")
      (value "Res3")
      (footprint "J1-0603")
      (description "Resistor")
      (fields (field (name "ALTIUM_VALUE") "10K") (field (name "PUBLISHER") "Altium Limited"))
      (libsource (lib "Miscellaneous Devices") (part "Res3"))
    )
    (comp (ref "R27")
      (value "Res3")
      (footprint "J1-0603")
      (description "Resistor")
      (fields (field (name "ALTIUM_VALUE") "10K") (field (name "PUBLISHER") "Altium Limited"))
      (libsource (lib "Miscellaneous Devices") (part "Res3"))
    )
    (comp (ref "R28")
      (value "Res3")
      (footprint "J1-0603")
      (description "Resistor")
      (fields (field (name "ALTIUM_VALUE") "10K") (field (name "PUBLISHER") "Altium Limited"))
      (libsource (lib "Miscellaneous Devices") (part "Res3"))
    )
    (comp (ref "R29")
      (value "Res3")
      (footprint "J1-0603")
      (description "Resistor")
      (fields (field (name "ALTIUM_VALUE") "8K") (field (name "PUBLISHER") "Altium Limited"))
      (libsource (lib "Miscellaneous Devices") (part "Res3"))
    )
    (comp (ref "R30")
      (value "Res3")
      (footprint "J1-0603")
      (description "Resistor")
      (fields (field (name "ALTIUM_VALUE") "10K") (field (name "PUBLISHER") "Altium Limited"))
      (libsource (lib "Miscellaneous Devices") (part "Res3"))
    )
    (comp (ref "R31")
      (value "Res3")
      (footprint "J1-0603")
      (description "Resistor")
      (fields (field (name "ALTIUM_VALUE") "1K") (field (name "PUBLISHER") "Altium Limited"))
      (libsource (lib "Miscellaneous Devices") (part "Res3"))
    )
    (comp (ref "R32")
      (value "Res3")
      (footprint "J1-0603")
      (description "Resistor")
      (fields (field (name "ALTIUM_VALUE") "27") (field (name "PUBLISHER") "Altium Limited"))
      (libsource (lib "Miscellaneous Devices") (part "Res3"))
    )
    (comp (ref "R33")
      (value "Res3")
      (footprint "J1-0603")
      (description "Resistor")
      (fields (field (name "ALTIUM_VALUE") "8K") (field (name "PUBLISHER") "Altium Limited"))
      (libsource (lib "Miscellaneous Devices") (part "Res3"))
    )
    (comp (ref "R34")
      (value "Res3")
      (footprint "J1-0603")
      (description "Resistor")
      (fields (field (name "ALTIUM_VALUE") "47") (field (name "PUBLISHER") "Altium Limited"))
      (libsource (lib "Miscellaneous Devices") (part "Res3"))
    )
    (comp (ref "R35")
      (value "Res3")
      (footprint "J1-0603")
      (description "Resistor")
      (fields (field (name "ALTIUM_VALUE") "27") (field (name "PUBLISHER") "Altium Limited"))
      (libsource (lib "Miscellaneous Devices") (part "Res3"))
    )
    (comp (ref "R36")
      (value "Res3")
      (footprint "J1-0603")
      (description "Resistor")
      (fields (field (name "ALTIUM_VALUE") "27") (field (name "PUBLISHER") "Altium Limited"))
      (libsource (lib "Miscellaneous Devices") (part "Res3"))
    )
    (comp (ref "R37")
      (value "Res3")
      (footprint "J1-0603")
      (description "Resistor")
      (fields (field (name "ALTIUM_VALUE") "47") (field (name "PUBLISHER") "Altium Limited"))
      (libsource (lib "Miscellaneous Devices") (part "Res3"))
    )
    (comp (ref "R38")
      (value "Res3")
      (footprint "J1-0603")
      (description "Resistor")
      (fields (field (name "ALTIUM_VALUE") "1K") (field (name "PUBLISHER") "Altium Limited"))
      (libsource (lib "Miscellaneous Devices") (part "Res3"))
    )
    (comp (ref "R39")
      (value "Res3")
      (footprint "J1-0603")
      (description "Resistor")
      (fields (field (name "ALTIUM_VALUE") "0") (field (name "PUBLISHER") "Altium Limited"))
      (libsource (lib "Miscellaneous Devices") (part "Res3"))
    )
    (comp (ref "R40")
      (value "Res3")
      (footprint "J1-0603")
      (description "Resistor")
      (fields (field (name "ALTIUM_VALUE") "1K") (field (name "PUBLISHER") "Altium Limited"))
      (libsource (lib "Miscellaneous Devices") (part "Res3"))
    )
    (comp (ref "R41")
      (value "Res3")
      (footprint "J1-0603")
      (description "Resistor")
      (fields (field (name "ALTIUM_VALUE") "0") (field (name "PUBLISHER") "Altium Limited"))
      (libsource (lib "Miscellaneous Devices") (part "Res3"))
    )
    (comp (ref "R42")
      (value "Res3")
      (footprint "J1-0603")
      (description "Resistor")
      (fields (field (name "ALTIUM_VALUE") "1K") (field (name "PUBLISHER") "Altium Limited"))
      (libsource (lib "Miscellaneous Devices") (part "Res3"))
    )
    (comp (ref "R43")
      (value "Res3")
      (footprint "J1-0603")
      (description "Resistor")
      (fields (field (name "ALTIUM_VALUE") "1K") (field (name "PUBLISHER") "Altium Limited"))
      (libsource (lib "Miscellaneous Devices") (part "Res3"))
    )
    (comp (ref "R44")
      (value "Res3")
      (footprint "J1-0603")
      (description "Resistor")
      (fields (field (name "ALTIUM_VALUE") "1K") (field (name "PUBLISHER") "Altium Limited"))
      (libsource (lib "Miscellaneous Devices") (part "Res3"))
    )
    (comp (ref "R45")
      (value "Res3")
      (footprint "J1-0603")
      (description "Resistor")
      (fields (field (name "ALTIUM_VALUE") "0") (field (name "PUBLISHER") "Altium Limited"))
      (libsource (lib "Miscellaneous Devices") (part "Res3"))
    )
    (comp (ref "R46")
      (value "Res3")
      (footprint "J1-0603")
      (description "Resistor")
      (fields (field (name "ALTIUM_VALUE") "0") (field (name "PUBLISHER") "Altium Limited"))
      (libsource (lib "Miscellaneous Devices") (part "Res3"))
    )
    (comp (ref "R47")
      (value "Res3")
      (footprint "J1-0603")
      (description "Resistor")
      (fields (field (name "ALTIUM_VALUE") "0") (field (name "PUBLISHER") "Altium Limited"))
      (libsource (lib "Miscellaneous Devices") (part "Res3"))
    )
    (comp (ref "R48")
      (value "Res3")
      (footprint "J1-0603")
      (description "Resistor")
      (fields (field (name "ALTIUM_VALUE") "1K") (field (name "PUBLISHER") "Altium Limited"))
      (libsource (lib "Miscellaneous Devices") (part "Res3"))
    )
    (comp (ref "R49")
      (value "Res3")
      (footprint "J1-0603")
      (description "Resistor")
      (fields (field (name "ALTIUM_VALUE") "0") (field (name "PUBLISHER") "Altium Limited"))
      (libsource (lib "Miscellaneous Devices") (part "Res3"))
    )
    (comp (ref "R50")
      (value "Res3")
      (footprint "J1-0603")
      (description "Resistor")
      (fields (field (name "ALTIUM_VALUE") "0") (field (name "PUBLISHER") "Altium Limited"))
      (libsource (lib "Miscellaneous Devices") (part "Res3"))
    )
    (comp (ref "R51")
      (value "Res3")
      (footprint "J1-0603")
      (description "Resistor")
      (fields (field (name "ALTIUM_VALUE") "0") (field (name "PUBLISHER") "Altium Limited"))
      (libsource (lib "Miscellaneous Devices") (part "Res3"))
    )
    (comp (ref "R52")
      (value "Res3")
      (footprint "J1-0603")
      (description "Resistor")
      (fields (field (name "ALTIUM_VALUE") "500") (field (name "PUBLISHER") "Altium Limited"))
      (libsource (lib "Miscellaneous Devices") (part "Res3"))
    )
    (comp (ref "R53")
      (value "Res3")
      (footprint "J1-0603")
      (description "Resistor")
      (fields (field (name "ALTIUM_VALUE") "1K") (field (name "PUBLISHER") "Altium Limited"))
      (libsource (lib "Miscellaneous Devices") (part "Res3"))
    )
    (comp (ref "R54")
      (value "Res3")
      (footprint "J1-0603")
      (description "Resistor")
      (fields (field (name "ALTIUM_VALUE") "1K") (field (name "PUBLISHER") "Altium Limited"))
      (libsource (lib "Miscellaneous Devices") (part "Res3"))
    )
    (comp (ref "R55")
      (value "10K")
      (footprint "J1-0603")
      (description "Resistor")
      (fields (field (name "Comment") "Res3") (field (name "PUBLISHER") "Altium Limited"))
      (libsource (lib "Miscellaneous Devices") (part "Res3"))
    )
    (comp (ref "R56")
      (value "10K")
      (footprint "J1-0603")
      (description "Resistor")
      (fields (field (name "Comment") "Res3") (field (name "PUBLISHER") "Altium Limited"))
      (libsource (lib "Miscellaneous Devices") (part "Res3"))
    )
    (comp (ref "R57")
      (value "10K")
      (footprint "J1-0603")
      (description "Resistor")
      (fields (field (name "Comment") "Res3") (field (name "PUBLISHER") "Altium Limited"))
      (libsource (lib "Miscellaneous Devices") (part "Res3"))
    )
    (comp (ref "R58")
      (value "10K")
      (footprint "J1-0603")
      (description "Resistor")
      (fields (field (name "Comment") "Res3") (field (name "PUBLISHER") "Altium Limited"))
      (libsource (lib "Miscellaneous Devices") (part "Res3"))
    )
    (comp (ref "R59")
      (value "Res3")
      (footprint "J1-0603")
      (description "Resistor")
      (fields (field (name "ALTIUM_VALUE") "50") (field (name "PUBLISHER") "Altium Limited"))
      (libsource (lib "Miscellaneous Devices") (part "Res3"))
    )
    (comp (ref "R60")
      (value "Res3")
      (footprint "J1-0603")
      (description "Resistor")
      (fields (field (name "ALTIUM_VALUE") "0") (field (name "PUBLISHER") "Altium Limited"))
      (libsource (lib "Miscellaneous Devices") (part "Res3"))
    )
    (comp (ref "R61")
      (value "Res3")
      (footprint "J1-0603")
      (description "Resistor")
      (fields (field (name "ALTIUM_VALUE") "0") (field (name "PUBLISHER") "Altium Limited"))
      (libsource (lib "Miscellaneous Devices") (part "Res3"))
    )
    (comp (ref "U1")
      (value "AMS1117-ADJ")
      (footprint "SOT-223")
      (libsource (lib "AMS1117") (part "AMS1117-ADJ"))
    )
    (comp (ref "U2")
      (value "AMS1117-1.2V")
      (footprint "SOT-223")
      (libsource (lib "AMS1117") (part "AMS1117-1.2V"))
    )
    (comp (ref "U3")
      (value "AMS1117-ADJ")
      (footprint "SOT-223")
      (libsource (lib "AMS1117") (part "AMS1117-ADJ"))
    )
    (comp (ref "U4")
      (value "M25P16-VMN3PB")
      (footprint "MICT-MN-8_N")
      (description "16 Mb (x1) Automotive Serial NOR Flash Memory, 75 MHz, 2.7 to 3.6 V, 8-pin SO8 Narrow (MN), Tube")
      (fields (field (name "VOLTAGE") "2.7V-3.6V ") (field (name "MANUFACTURER") "Micron"))
      (libsource (lib "Micron Memory Serial NOR Flash") (part "M25P16-VMN3PB"))
    )
    (comp (ref "U5")
      (value "FT232RL-Reel")
      (footprint "SSOP-28_N")
      (description "USB UART Asynchronous Serial Data Transfer Chip, 28-pin SSOP, Tape and Reel")
      (fields (field (name "MANUFACTURER") "FTDI"))
      (libsource (lib "FTDI FT Series") (part "FT232RL-Reel"))
    )
    (comp (ref "U6")
      (value "BSS138")
      (footprint "SOT-23")
      (description "BSS138 SOT-23")
      (libsource (lib "BSS138") (part "BSS138"))
    )
    (comp (ref "U7")
      (value "BSS138")
      (footprint "SOT-23")
      (description "BSS138 SOT-23")
      (libsource (lib "BSS138") (part "BSS138"))
    )
    (comp (ref "U8")
      (value "BSS138")
      (footprint "SOT-23")
      (description "BSS138 SOT-23")
      (libsource (lib "BSS138") (part "BSS138"))
    )
    (comp (ref "U9")
      (value "BSS138")
      (footprint "SOT-23")
      (description "BSS138 SOT-23")
      (libsource (lib "BSS138") (part "BSS138"))
    )
    (comp (ref "U10")
      (value "EP3C25Q240C8")
      (footprint "PQFP240_N")
      (description "Cyclone III Family FPGA, 148 I/O Pins, 4 PLLs, 240-Pin PQFP, Speed Grade 8, Commercial Grade")
      (fields (field (name "PUBLISHER") "Altium Limited"))
      (libsource (lib "Altera Cyclone III") (part "EP3C25Q240C8"))
    )
    (comp (ref "U11")
      (value "M25P16-VMN3PB")
      (footprint "MICT-MN-8_N")
      (description "16 Mb (x1) Automotive Serial NOR Flash Memory, 75 MHz, 2.7 to 3.6 V, 8-pin SO8 Narrow (MN), Tube")
      (fields (field (name "VOLTAGE") "2.7V-3.6V ") (field (name "MANUFACTURER") "Micron"))
      (libsource (lib "Micron Memory Serial NOR Flash") (part "M25P16-VMN3PB"))
    )
    (comp (ref "U12")
      (value "MT48LC4M32B2TG-7")
      (footprint "MICT-TG-86_N")
      (description "128Mb PC133 SDR SDRAM, 4Mb x 32, 7ns, 3.3V, 0 to 70 degC, 86-Pin TSOP")
      (fields (field (name "VOLTAGE") "3.3V ") (field (name "MANUFACTURER") "Micron"))
      (libsource (lib "Micron Memory SDRAM") (part "MT48LC4M32B2TG-7"))
    )
    (comp (ref "Y1")
      (value "Abracon XO ASE")
      (footprint "ABRACON ASE")
      (description "SMD CMOS Crystal Oscillator")
      (libsource (lib "ABRACON ASE") (part "Abracon XO ASE"))
    )
  )
  (nets
    (net (code "1") (name "/ASDO") (class "Default")
      (node (ref "U10") (pin "12") (pinfunction "IO,_(DATA1,_ASDO)_12") (pintype "bidirectional"))
      (node (ref "U11") (pin "5") (pinfunction "DQ0_5") (pintype "input"))
    )
    (net (code "2") (name "/AUDIO_LEFT") (class "Default")
      (node (ref "C11") (pin "2") (pinfunction "2_2") (pintype "passive"))
      (node (ref "P2") (pin "14") (pinfunction "14_14") (pintype "passive"))
      (node (ref "R33") (pin "2") (pinfunction "2_2") (pintype "passive"))
    )
    (net (code "3") (name "/AUDIO_RIGHT") (class "Default")
      (node (ref "C10") (pin "2") (pinfunction "2_2") (pintype "passive"))
      (node (ref "P2") (pin "15") (pinfunction "15_15") (pintype "passive"))
      (node (ref "R29") (pin "2") (pinfunction "2_2") (pintype "passive"))
    )
    (net (code "4") (name "/CLK_50M") (class "Default")
      (node (ref "R59") (pin "2") (pinfunction "2_2") (pintype "passive"))
      (node (ref "Y1") (pin "3") (pinfunction "OUT_3") (pintype "output"))
    )
    (net (code "5") (name "/CLK_TRI") (class "Default")
      (node (ref "R60") (pin "2") (pinfunction "2_2") (pintype "passive"))
      (node (ref "R61") (pin "1") (pinfunction "1_1") (pintype "passive"))
      (node (ref "Y1") (pin "1") (pinfunction "TRI_1") (pintype "input"))
    )
    (net (code "6") (name "/CONF_DONE") (class "Default")
      (node (ref "R58") (pin "2") (pinfunction "2_2") (pintype "passive"))
      (node (ref "U10") (pin "153") (pinfunction "CONF_DONE_153") (pintype "bidirectional"))
    )
    (net (code "7") (name "/DATA0") (class "Default")
      (node (ref "R32") (pin "2") (pinfunction "2_2") (pintype "passive"))
      (node (ref "U10") (pin "24") (pinfunction "IO,_(DATA0)_24") (pintype "bidirectional"))
    )
    (net (code "8") (name "/DCLK") (class "Default")
      (node (ref "U10") (pin "23") (pinfunction "DCLK_23") (pintype "bidirectional"))
      (node (ref "U11") (pin "6") (pinfunction "C_6") (pintype "input"))
    )
    (net (code "9") (name "/DIG_B0") (class "Default")
      (node (ref "R52") (pin "1") (pinfunction "1_1") (pintype "passive"))
      (node (ref "R53") (pin "1") (pinfunction "1_1") (pintype "passive"))
      (node (ref "U10") (pin "231") (pinfunction "IO,_DIFFIO_T6p,_(DATA6),_(DQ5T)_231") (pintype "bidirectional"))
    )
    (net (code "10") (name "/DIG_B1") (class "Default")
      (node (ref "R54") (pin "1") (pinfunction "1_1") (pintype "passive"))
      (node (ref "U10") (pin "230") (pinfunction "IO,_DIFFIO_T6n_230") (pintype "bidirectional"))
    )
    (net (code "11") (name "/DIG_G0") (class "Default")
      (node (ref "R43") (pin "1") (pinfunction "1_1") (pintype "passive"))
      (node (ref "R44") (pin "1") (pinfunction "1_1") (pintype "passive"))
      (node (ref "U10") (pin "233") (pinfunction "IO,_(DATA11)_233") (pintype "bidirectional"))
    )
    (net (code "12") (name "/DIG_G1") (class "Default")
      (node (ref "R48") (pin "1") (pinfunction "1_1") (pintype "passive"))
      (node (ref "U10") (pin "232") (pinfunction "IO,_(DATA7),_(DM5T/BWS#5T)_232") (pintype "bidirectional"))
    )
    (net (code "13") (name "/DIG_HSYNC") (class "Default")
      (node (ref "R37") (pin "2") (pinfunction "2_2") (pintype "passive"))
      (node (ref "U10") (pin "224") (pinfunction "IO,_(DATA14),_(DQS3T/CQ3T#,DPCLK11)_224") (pintype "bidirectional"))
    )
    (net (code "14") (name "/DIG_R0") (class "Default")
      (node (ref "R38") (pin "1") (pinfunction "1_1") (pintype "passive"))
      (node (ref "R40") (pin "1") (pinfunction "1_1") (pintype "passive"))
      (node (ref "U10") (pin "235") (pinfunction "IO,_DIFFIO_T2p_235") (pintype "bidirectional"))
    )
    (net (code "15") (name "/DIG_R1") (class "Default")
      (node (ref "R42") (pin "1") (pinfunction "1_1") (pintype "passive"))
      (node (ref "U10") (pin "234") (pinfunction "IO,_DIFFIO_T2n_234") (pintype "bidirectional"))
    )
    (net (code "16") (name "/DIG_VSYNC") (class "Default")
      (node (ref "R34") (pin "2") (pinfunction "2_2") (pintype "passive"))
      (node (ref "U10") (pin "226") (pinfunction "IO,_(DATA5),_(DQ5T)_226") (pintype "bidirectional"))
    )
    (net (code "17") (name "/ETH_CS") (class "Default")
      (node (ref "P4") (pin "7") (pinfunction "7_7") (pintype "passive"))
      (node (ref "U10") (pin "202") (pinfunction "IO,_DIFFIO_T15n,_(PADD7),_(DQ5T)_202") (pintype "bidirectional"))
    )
    (net (code "18") (name "/ETH_INT") (class "Default")
      (node (ref "P4") (pin "2") (pinfunction "2_2") (pintype "passive"))
      (node (ref "U10") (pin "217") (pinfunction "IO,_(DQ5T)_217") (pintype "bidirectional"))
    )
    (net (code "19") (name "/ETH_RESET") (class "Default")
      (node (ref "P4") (pin "8") (pinfunction "8_8") (pintype "passive"))
      (node (ref "U10") (pin "203") (pinfunction "IO,_DIFFIO_T15p,_(PADD8)_203") (pintype "bidirectional"))
    )
    (net (code "20") (name "/ETH_SCK") (class "Default")
      (node (ref "P4") (pin "6") (pinfunction "6_6") (pintype "passive"))
      (node (ref "U10") (pin "214") (pinfunction "IO,_(PADD17),_(DQS5T/CQ5T#,DPCLK10)_214") (pintype "bidirectional"))
    )
    (net (code "21") (name "/ETH_SI") (class "Default")
      (node (ref "P4") (pin "5") (pinfunction "5_5") (pintype "passive"))
      (node (ref "U10") (pin "207") (pinfunction "IO,_(PADD12),_(DQS4T/CQ5T,DPCLK9)_207") (pintype "bidirectional"))
    )
    (net (code "22") (name "/ETH_SO") (class "Default")
      (node (ref "P4") (pin "4") (pinfunction "4_4") (pintype "passive"))
      (node (ref "U10") (pin "216") (pinfunction "IO_216") (pintype "bidirectional"))
    )
    (net (code "23") (name "/FLASH_DQ1") (class "Default")
      (node (ref "R32") (pin "1") (pinfunction "1_1") (pintype "passive"))
      (node (ref "U11") (pin "2") (pinfunction "DQ1_2") (pintype "tri_state"))
    )
    (net (code "24") (name "/FPGA_FT232_RX") (class "Default")
      (node (ref "U10") (pin "145") (pinfunction "IO,_DIFFIO_R9p,_(DEV_CLRn)_145") (pintype "bidirectional"))
      (node (ref "U5") (pin "1") (pinfunction "TXD_1") (pintype "output"))
    )
    (net (code "25") (name "/FPGA_FT232_TX") (class "Default")
      (node (ref "U10") (pin "146") (pinfunction "IO_146") (pintype "bidirectional"))
      (node (ref "U5") (pin "5") (pinfunction "RXD_5") (pintype "input"))
    )
    (net (code "26") (name "/FPGA_KBD_CLOCK") (class "Default")
      (node (ref "D6") (pin "3") (pintype "passive"))
      (node (ref "R10") (pin "2") (pinfunction "2_2") (pintype "passive"))
      (node (ref "R17") (pin "1") (pinfunction "1_1") (pintype "passive"))
      (node (ref "U10") (pin "223") (pinfunction "IO,_VREFB8N0_223") (pintype "bidirectional"))
      (node (ref "U7") (pin "2") (pinfunction "S_2") (pintype "passive"))
    )
    (net (code "27") (name "/FPGA_KBD_DATA") (class "Default")
      (node (ref "D5") (pin "3") (pintype "passive"))
      (node (ref "R15") (pin "1") (pinfunction "1_1") (pintype "passive"))
      (node (ref "R9") (pin "2") (pinfunction "2_2") (pintype "passive"))
      (node (ref "U10") (pin "221") (pinfunction "IO,_(DATA4),_(DQ5T)_221") (pintype "bidirectional"))
      (node (ref "U6") (pin "2") (pinfunction "S_2") (pintype "passive"))
    )
    (net (code "28") (name "/FPGA_MOUSE_CLOCK") (class "Default")
      (node (ref "D8") (pin "3") (pintype "passive"))
      (node (ref "R12") (pin "2") (pinfunction "2_2") (pintype "passive"))
      (node (ref "R22") (pin "1") (pinfunction "1_1") (pintype "passive"))
      (node (ref "U10") (pin "219") (pinfunction "IO,_DIFFIO_T10p,_(DATA3),_(DQ5T)_219") (pintype "bidirectional"))
      (node (ref "U9") (pin "2") (pinfunction "S_2") (pintype "passive"))
    )
    (net (code "29") (name "/FPGA_MOUSE_DATA") (class "Default")
      (node (ref "D7") (pin "3") (pintype "passive"))
      (node (ref "R11") (pin "2") (pinfunction "2_2") (pintype "passive"))
      (node (ref "R19") (pin "1") (pinfunction "1_1") (pintype "passive"))
      (node (ref "U10") (pin "218") (pinfunction "IO,_DIFFIO_T10n,_(DATA2)_218") (pintype "bidirectional"))
      (node (ref "U8") (pin "2") (pinfunction "S_2") (pintype "passive"))
    )
    (net (code "30") (name "/FPGA_TCK") (class "Default")
      (node (ref "R36") (pin "2") (pinfunction "2_2") (pintype "passive"))
      (node (ref "U10") (pin "27") (pinfunction "TCK_27") (pintype "input"))
    )
    (net (code "31") (name "/FPGA_TDI") (class "Default")
      (node (ref "R35") (pin "2") (pinfunction "2_2") (pintype "passive"))
      (node (ref "U10") (pin "26") (pinfunction "TDI_26") (pintype "input"))
    )
    (net (code "32") (name "/GPIO0_0") (class "Default")
      (node (ref "P2") (pin "12") (pinfunction "12_12") (pintype "passive"))
      (node (ref "U10") (pin "159") (pinfunction "IO,_DIFFIO_R5n,_(INIT_DONE)_159") (pintype "bidirectional"))
    )
    (net (code "33") (name "/GPIO0_1") (class "Default")
      (node (ref "P2") (pin "11") (pinfunction "11_11") (pintype "passive"))
      (node (ref "U10") (pin "160") (pinfunction "IO,_DIFFIO_R5p,_(CRC_ERROR)_160") (pintype "bidirectional"))
    )
    (net (code "34") (name "/GPIO0_2") (class "Default")
      (node (ref "P2") (pin "10") (pinfunction "10_10") (pintype "passive"))
      (node (ref "U10") (pin "161") (pinfunction "IO_161") (pintype "bidirectional"))
    )
    (net (code "35") (name "/GPIO0_3") (class "Default")
      (node (ref "P2") (pin "9") (pinfunction "9_9") (pintype "passive"))
      (node (ref "U10") (pin "162") (pinfunction "IO,_DIFFIO_R4n,_(nCEO)_162") (pintype "bidirectional"))
    )
    (net (code "36") (name "/GPIO0_4") (class "Default")
      (node (ref "P2") (pin "8") (pinfunction "8_8") (pintype "passive"))
      (node (ref "U10") (pin "164") (pinfunction "IO,_DIFFIO_R4p,_(CLKUSR)_164") (pintype "bidirectional"))
    )
    (net (code "37") (name "/GPIO0_5") (class "Default")
      (node (ref "P2") (pin "7") (pinfunction "7_7") (pintype "passive"))
      (node (ref "U10") (pin "166") (pinfunction "IO,_(DQS0R/CQ1R,DPCLK7)_166") (pintype "bidirectional"))
    )
    (net (code "38") (name "/GPIO0_6") (class "Default")
      (node (ref "P2") (pin "6") (pinfunction "6_6") (pintype "passive"))
      (node (ref "U10") (pin "167") (pinfunction "IO,_DIFFIO_R3n,_(nWE)_167") (pintype "bidirectional"))
    )
    (net (code "39") (name "/GPIO0_7") (class "Default")
      (node (ref "P2") (pin "5") (pinfunction "5_5") (pintype "passive"))
      (node (ref "U10") (pin "168") (pinfunction "IO,_DIFFIO_R3p,_(nOE)_168") (pintype "bidirectional"))
    )
    (net (code "40") (name "/GPIO0_8") (class "Default")
      (node (ref "P2") (pin "4") (pinfunction "4_4") (pintype "passive"))
      (node (ref "U10") (pin "171") (pinfunction "IO,_(RDY),_(DQ1R)_171") (pintype "bidirectional"))
    )
    (net (code "41") (name "/GPIO0_9") (class "Default")
      (node (ref "P2") (pin "3") (pinfunction "3_3") (pintype "passive"))
      (node (ref "U10") (pin "173") (pinfunction "IO,_(PADD23)_173") (pintype "bidirectional"))
    )
    (net (code "42") (name "/GPIO0_10") (class "Default")
      (node (ref "P2") (pin "2") (pinfunction "2_2") (pintype "passive"))
      (node (ref "U10") (pin "176") (pinfunction "IO,_DIFFIO_R1n,_(PADD20),_(DQS2R/CQ3R,CDPCLK5)_176") (pintype "bidirectional"))
    )
    (net (code "43") (name "/GPIO0_11") (class "Default")
      (node (ref "P2") (pin "1") (pinfunction "1_1") (pintype "passive"))
      (node (ref "U10") (pin "177") (pinfunction "IO,_DIFFIO_R1p_177") (pintype "bidirectional"))
    )
    (net (code "44") (name "/JTAG_TCK") (class "Default")
      (node (ref "J5") (pin "1") (pinfunction "1_1") (pintype "passive"))
      (node (ref "R36") (pin "1") (pinfunction "1_1") (pintype "passive"))
    )
    (net (code "45") (name "/JTAG_TDI") (class "Default")
      (node (ref "J5") (pin "9") (pinfunction "9_9") (pintype "passive"))
      (node (ref "R35") (pin "1") (pinfunction "1_1") (pintype "passive"))
    )
    (net (code "46") (name "/JTAG_TDO") (class "Default")
      (node (ref "J5") (pin "3") (pinfunction "3_3") (pintype "passive"))
      (node (ref "U10") (pin "29") (pinfunction "TDO_29") (pintype "output"))
    )
    (net (code "47") (name "/JTAG_TMS") (class "Default")
      (node (ref "J5") (pin "5") (pinfunction "5_5") (pintype "passive"))
      (node (ref "U10") (pin "28") (pinfunction "TMS_28") (pintype "input"))
    )
    (net (code "48") (name "/KBD_CLOCK") (class "Default")
      (node (ref "J3") (pin "5") (pinfunction "PS/2_Clock_5") (pintype "bidirectional"))
      (node (ref "R10") (pin "1") (pinfunction "1_1") (pintype "passive"))
      (node (ref "R18") (pin "1") (pinfunction "1_1") (pintype "passive"))
      (node (ref "U7") (pin "3") (pinfunction "D_3") (pintype "passive"))
    )
    (net (code "49") (name "/KBD_DATA") (class "Default")
      (node (ref "J3") (pin "1") (pinfunction "PS/2_Data_1") (pintype "bidirectional"))
      (node (ref "R16") (pin "1") (pinfunction "1_1") (pintype "passive"))
      (node (ref "R9") (pin "1") (pinfunction "1_1") (pintype "passive"))
      (node (ref "U6") (pin "3") (pinfunction "D_3") (pintype "passive"))
    )
    (net (code "50") (name "/LED0") (class "Default")
      (node (ref "D9") (pin "1") (pinfunction "A_1") (pintype "passive"))
      (node (ref "U10") (pin "237") (pinfunction "IO,_DIFFIO_T1n_237") (pintype "bidirectional"))
    )
    (net (code "51") (name "/LED1") (class "Default")
      (node (ref "D10") (pin "1") (pinfunction "A_1") (pintype "passive"))
      (node (ref "U10") (pin "236") (pinfunction "IO,_(DATA12),_(DQS1T/CQ1T#,CDPCLK7)_236") (pintype "bidirectional"))
    )
    (net (code "52") (name "/MICROSD_CLK") (class "Default")
      (node (ref "J4") (pin "5") (pinfunction "5_5") (pintype "bidirectional"))
      (node (ref "U10") (pin "139") (pinfunction "IO,_DIFFIO_R11p_139") (pintype "bidirectional"))
    )
    (net (code "53") (name "/MICROSD_CMD") (class "Default")
      (node (ref "J4") (pin "3") (pinfunction "3_3") (pintype "bidirectional"))
      (node (ref "U10") (pin "142") (pinfunction "IO,_DIFFIO_R10n_142") (pintype "bidirectional"))
    )
    (net (code "54") (name "/MICROSD_DAT0") (class "Default")
      (node (ref "J4") (pin "7") (pinfunction "7_7") (pintype "bidirectional"))
      (node (ref "U10") (pin "137") (pinfunction "IO,_DIFFIO_R11n,_(DQ1R)_137") (pintype "bidirectional"))
    )
    (net (code "55") (name "/MICROSD_DAT1") (class "Default")
      (node (ref "J4") (pin "8") (pinfunction "8_8") (pintype "bidirectional"))
      (node (ref "U10") (pin "135") (pinfunction "IO,_DIFFIO_R12p,_(DQ1R)_135") (pintype "bidirectional"))
    )
    (net (code "56") (name "/MICROSD_DAT2") (class "Default")
      (node (ref "J4") (pin "1") (pinfunction "1_1") (pintype "bidirectional"))
      (node (ref "U10") (pin "144") (pinfunction "IO,_DIFFIO_R9n,_(DEV_OE)_144") (pintype "bidirectional"))
    )
    (net (code "57") (name "/MICROSD_DAT3") (class "Default")
      (node (ref "J4") (pin "2") (pinfunction "2_2") (pintype "bidirectional"))
      (node (ref "U10") (pin "143") (pinfunction "IO,_DIFFIO_R10p,_(DQS1R/CQ1R#,DPCLK6)_143") (pintype "bidirectional"))
    )
    (net (code "58") (name "/MOUSE_CLOCK") (class "Default")
      (node (ref "J1") (pin "5") (pinfunction "PS/2_Clock_5") (pintype "bidirectional"))
      (node (ref "R12") (pin "1") (pinfunction "1_1") (pintype "passive"))
      (node (ref "R23") (pin "1") (pinfunction "1_1") (pintype "passive"))
      (node (ref "U9") (pin "3") (pinfunction "D_3") (pintype "passive"))
    )
    (net (code "59") (name "/MOUSE_DATA") (class "Default")
      (node (ref "J1") (pin "1") (pinfunction "PS/2_Data_1") (pintype "bidirectional"))
      (node (ref "R11") (pin "1") (pinfunction "1_1") (pintype "passive"))
      (node (ref "R20") (pin "1") (pinfunction "1_1") (pintype "passive"))
      (node (ref "U8") (pin "3") (pinfunction "D_3") (pintype "passive"))
    )
    (net (code "60") (name "/MSEL0") (class "Default")
      (node (ref "R45") (pin "1") (pinfunction "1_1") (pintype "passive"))
      (node (ref "R49") (pin "2") (pinfunction "2_2") (pintype "passive"))
      (node (ref "U10") (pin "155") (pinfunction "MSEL0_155") (pintype "input"))
    )
    (net (code "61") (name "/MSEL1") (class "Default")
      (node (ref "R46") (pin "1") (pinfunction "1_1") (pintype "passive"))
      (node (ref "R50") (pin "2") (pinfunction "2_2") (pintype "passive"))
      (node (ref "U10") (pin "157") (pinfunction "MSEL1_157") (pintype "input"))
    )
    (net (code "62") (name "/MSEL2") (class "Default")
      (node (ref "R47") (pin "1") (pinfunction "1_1") (pintype "passive"))
      (node (ref "R51") (pin "2") (pinfunction "2_2") (pintype "passive"))
      (node (ref "U10") (pin "158") (pinfunction "MSEL2_158") (pintype "input"))
    )
    (net (code "63") (name "/PWM_LEFT") (class "Default")
      (node (ref "R33") (pin "1") (pinfunction "1_1") (pintype "passive"))
      (node (ref "U10") (pin "148") (pinfunction "IO,_DIFFIO_R7p_148") (pintype "bidirectional"))
    )
    (net (code "64") (name "/PWM_RIGHT") (class "Default")
      (node (ref "R29") (pin "1") (pinfunction "1_1") (pintype "passive"))
      (node (ref "U10") (pin "147") (pinfunction "IO,_DIFFIO_R7n_147") (pintype "bidirectional"))
    )
    (net (code "65") (name "/SDRAM_A0") (class "Default")
      (node (ref "U10") (pin "113") (pinfunction "IO,_(DQS0B/CQ1B,CDPCLK3)_113") (pintype "bidirectional"))
      (node (ref "U12") (pin "25") (pinfunction "A0_25") (pintype "input"))
    )
    (net (code "66") (name "/SDRAM_A1") (class "Default")
      (node (ref "U10") (pin "114") (pinfunction "IO_114") (pintype "bidirectional"))
      (node (ref "U12") (pin "26") (pinfunction "A1_26") (pintype "input"))
    )
    (net (code "67") (name "/SDRAM_A2") (class "Default")
      (node (ref "U10") (pin "117") (pinfunction "IO,_PLL4_CLKOUTp_117") (pintype "bidirectional"))
      (node (ref "U12") (pin "27") (pinfunction "A2_27") (pintype "input"))
    )
    (net (code "68") (name "/SDRAM_A3") (class "Default")
      (node (ref "U10") (pin "93") (pinfunction "IO,_DIFFIO_B13p,_(DQ5B)_93") (pintype "bidirectional"))
      (node (ref "U12") (pin "60") (pinfunction "A3_60") (pintype "input"))
    )
    (net (code "69") (name "/SDRAM_A4") (class "Default")
      (node (ref "U10") (pin "88") (pinfunction "IO,_(DQ5B)_88") (pintype "bidirectional"))
      (node (ref "U12") (pin "61") (pinfunction "A4_61") (pintype "input"))
    )
    (net (code "70") (name "/SDRAM_A5") (class "Default")
      (node (ref "U10") (pin "87") (pinfunction "IO,_(DQ5B)_87") (pintype "bidirectional"))
      (node (ref "U12") (pin "62") (pinfunction "A5_62") (pintype "input"))
    )
    (net (code "71") (name "/SDRAM_A6") (class "Default")
      (node (ref "U10") (pin "84") (pinfunction "IO_84") (pintype "bidirectional"))
      (node (ref "U12") (pin "63") (pinfunction "A6_63") (pintype "input"))
    )
    (net (code "72") (name "/SDRAM_A7") (class "Default")
      (node (ref "U10") (pin "83") (pinfunction "IO,_(DQS5B/CQ5B#,DPCLK3)_83") (pintype "bidirectional"))
      (node (ref "U12") (pin "64") (pinfunction "A7_64") (pintype "input"))
    )
    (net (code "73") (name "/SDRAM_A8") (class "Default")
      (node (ref "U10") (pin "82") (pinfunction "IO,_DIFFIO_B7n,_(DQ5B)_82") (pintype "bidirectional"))
      (node (ref "U12") (pin "65") (pinfunction "A8_65") (pintype "input"))
    )
    (net (code "74") (name "/SDRAM_A9") (class "Default")
      (node (ref "U10") (pin "81") (pinfunction "IO,_DIFFIO_B7p,_(DQ5B)_81") (pintype "bidirectional"))
      (node (ref "U12") (pin "66") (pinfunction "A9_66") (pintype "input"))
    )
    (net (code "75") (name "/SDRAM_A10") (class "Default")
      (node (ref "U10") (pin "112") (pinfunction "IO,_RDN2_112") (pintype "bidirectional"))
      (node (ref "U12") (pin "24") (pinfunction "A10_24") (pintype "input"))
    )
    (net (code "76") (name "/SDRAM_A11") (class "Default")
      (node (ref "U10") (pin "57") (pinfunction "IO,_DIFFIO_L15n,_(DQ1L)_57") (pintype "bidirectional"))
      (node (ref "U12") (pin "21") (pinfunction "A11_21") (pintype "input"))
    )
    (net (code "77") (name "/SDRAM_BA0") (class "Default")
      (node (ref "U10") (pin "110") (pinfunction "IO_110") (pintype "bidirectional"))
      (node (ref "U12") (pin "22") (pinfunction "BA0_22") (pintype "input"))
    )
    (net (code "78") (name "/SDRAM_BA1") (class "Default")
      (node (ref "U10") (pin "111") (pinfunction "IO,_RUP2_111") (pintype "bidirectional"))
      (node (ref "U12") (pin "23") (pinfunction "BA1_23") (pintype "input"))
    )
    (net (code "79") (name "/SDRAM_CKE") (class "Default")
      (node (ref "U10") (pin "80") (pinfunction "IO,_(DM5B/BWS#5B)_80") (pintype "bidirectional"))
      (node (ref "U12") (pin "67") (pinfunction "CKE_67") (pintype "input"))
    )
    (net (code "80") (name "/SDRAM_CLK") (class "Default")
      (node (ref "U10") (pin "78") (pinfunction "IO,_(DQS3B/CQ3B#,DPCLK2)_78") (pintype "bidirectional"))
      (node (ref "U12") (pin "68") (pinfunction "CLK_68") (pintype "input"))
    )
    (net (code "81") (name "/SDRAM_DQ0") (class "Default")
      (node (ref "U10") (pin "37") (pinfunction "IO,_DIFFIO_L8p,_(DQ1L)_37") (pintype "bidirectional"))
      (node (ref "U12") (pin "2") (pinfunction "DQ0_2") (pintype "bidirectional"))
    )
    (net (code "82") (name "/SDRAM_DQ1") (class "Default")
      (node (ref "U10") (pin "38") (pinfunction "IO,_DIFFIO_L8n,_(DQ1L)_38") (pintype "bidirectional"))
      (node (ref "U12") (pin "4") (pinfunction "DQ1_4") (pintype "bidirectional"))
    )
    (net (code "83") (name "/SDRAM_DQ2") (class "Default")
      (node (ref "U10") (pin "39") (pinfunction "IO_39") (pintype "bidirectional"))
      (node (ref "U12") (pin "5") (pinfunction "DQ2_5") (pintype "bidirectional"))
    )
    (net (code "84") (name "/SDRAM_DQ3") (class "Default")
      (node (ref "U10") (pin "41") (pinfunction "IO,_DIFFIO_L10p,_(DQ1L)_41") (pintype "bidirectional"))
      (node (ref "U12") (pin "7") (pinfunction "DQ3_7") (pintype "bidirectional"))
    )
    (net (code "85") (name "/SDRAM_DQ4") (class "Default")
      (node (ref "U10") (pin "43") (pinfunction "IO,_DIFFIO_L10n,_(DQ1L)_43") (pintype "bidirectional"))
      (node (ref "U12") (pin "8") (pinfunction "DQ4_8") (pintype "bidirectional"))
    )
    (net (code "86") (name "/SDRAM_DQ5") (class "Default")
      (node (ref "U10") (pin "44") (pinfunction "IO,_DIFFIO_L11p,_(DQS1L/CQ1L#,DPCLK1)_44") (pintype "bidirectional"))
      (node (ref "U12") (pin "10") (pinfunction "DQ5_10") (pintype "bidirectional"))
    )
    (net (code "87") (name "/SDRAM_DQ6") (class "Default")
      (node (ref "U10") (pin "45") (pinfunction "IO,_DIFFIO_L11n,_(DQ1L)_45") (pintype "bidirectional"))
      (node (ref "U12") (pin "11") (pinfunction "DQ6_11") (pintype "bidirectional"))
    )
    (net (code "88") (name "/SDRAM_DQ7") (class "Default")
      (node (ref "U10") (pin "49") (pinfunction "IO,_DIFFIO_L13p,_(DQ1L)_49") (pintype "bidirectional"))
      (node (ref "U12") (pin "13") (pinfunction "DQ7_13") (pintype "bidirectional"))
    )
    (net (code "89") (name "/SDRAM_DQ8") (class "Default")
      (node (ref "U10") (pin "72") (pinfunction "IO,_DIFFIO_B4n_72") (pintype "bidirectional"))
      (node (ref "U12") (pin "74") (pinfunction "DQ8_74") (pintype "bidirectional"))
    )
    (net (code "90") (name "/SDRAM_DQ9") (class "Default")
      (node (ref "U10") (pin "71") (pinfunction "IO,_DIFFIO_B4p_71") (pintype "bidirectional"))
      (node (ref "U12") (pin "76") (pinfunction "DQ9_76") (pintype "bidirectional"))
    )
    (net (code "91") (name "/SDRAM_DQ10") (class "Default")
      (node (ref "U10") (pin "70") (pinfunction "IO,_PLL1_CLKOUTn_70") (pintype "bidirectional"))
      (node (ref "U12") (pin "77") (pinfunction "DQ10_77") (pintype "bidirectional"))
    )
    (net (code "92") (name "/SDRAM_DQ11") (class "Default")
      (node (ref "U10") (pin "69") (pinfunction "IO,_PLL1_CLKOUTp_69") (pintype "bidirectional"))
      (node (ref "U12") (pin "79") (pinfunction "DQ11_79") (pintype "bidirectional"))
    )
    (net (code "93") (name "/SDRAM_DQ12") (class "Default")
      (node (ref "U10") (pin "68") (pinfunction "IO,_(DQS1B/CQ1B#,CDPCLK2)_68") (pintype "bidirectional"))
      (node (ref "U12") (pin "80") (pinfunction "DQ12_80") (pintype "bidirectional"))
    )
    (net (code "94") (name "/SDRAM_DQ13") (class "Default")
      (node (ref "U10") (pin "65") (pinfunction "IO_65") (pintype "bidirectional"))
      (node (ref "U12") (pin "82") (pinfunction "DQ13_82") (pintype "bidirectional"))
    )
    (net (code "95") (name "/SDRAM_DQ14") (class "Default")
      (node (ref "U10") (pin "64") (pinfunction "IO,_DIFFIO_B2n_64") (pintype "bidirectional"))
      (node (ref "U12") (pin "83") (pinfunction "DQ14_83") (pintype "bidirectional"))
    )
    (net (code "96") (name "/SDRAM_DQ15") (class "Default")
      (node (ref "U10") (pin "63") (pinfunction "IO,_DIFFIO_B2p_63") (pintype "bidirectional"))
      (node (ref "U12") (pin "85") (pinfunction "DQ15_85") (pintype "bidirectional"))
    )
    (net (code "97") (name "/SDRAM_DQ16") (class "Default")
      (node (ref "U10") (pin "119") (pinfunction "IO,_DIFFIO_B25p_119") (pintype "bidirectional"))
      (node (ref "U12") (pin "31") (pinfunction "DQ16_31") (pintype "bidirectional"))
    )
    (net (code "98") (name "/SDRAM_DQ17") (class "Default")
      (node (ref "U10") (pin "120") (pinfunction "IO,_DIFFIO_B25n_120") (pintype "bidirectional"))
      (node (ref "U12") (pin "33") (pinfunction "DQ17_33") (pintype "bidirectional"))
    )
    (net (code "99") (name "/SDRAM_DQ18") (class "Default")
      (node (ref "U10") (pin "126") (pinfunction "IO,_RUP3,_(DQ1R)_126") (pintype "bidirectional"))
      (node (ref "U12") (pin "34") (pinfunction "DQ18_34") (pintype "bidirectional"))
    )
    (net (code "100") (name "/SDRAM_DQ19") (class "Default")
      (node (ref "U10") (pin "127") (pinfunction "IO,_RDN3,_(DQ1R)_127") (pintype "bidirectional"))
      (node (ref "U12") (pin "36") (pinfunction "DQ19_36") (pintype "bidirectional"))
    )
    (net (code "101") (name "/SDRAM_DQ20") (class "Default")
      (node (ref "U10") (pin "128") (pinfunction "IO,_(DQS3R/CQ3R#,CDPCLK4)_128") (pintype "bidirectional"))
      (node (ref "U12") (pin "37") (pinfunction "DQ20_37") (pintype "bidirectional"))
    )
    (net (code "102") (name "/SDRAM_DQ21") (class "Default")
      (node (ref "U10") (pin "131") (pinfunction "IO,_DIFFIO_R13n,_(DQ1R)_131") (pintype "bidirectional"))
      (node (ref "U12") (pin "39") (pinfunction "DQ21_39") (pintype "bidirectional"))
    )
    (net (code "103") (name "/SDRAM_DQ22") (class "Default")
      (node (ref "U10") (pin "132") (pinfunction "IO,_DIFFIO_R13p,_(DQ1R)_132") (pintype "bidirectional"))
      (node (ref "U12") (pin "40") (pinfunction "DQ22_40") (pintype "bidirectional"))
    )
    (net (code "104") (name "/SDRAM_DQ23") (class "Default")
      (node (ref "U10") (pin "134") (pinfunction "IO,_DIFFIO_R12n,_(DQ1R)_134") (pintype "bidirectional"))
      (node (ref "U12") (pin "42") (pinfunction "DQ23_42") (pintype "bidirectional"))
    )
    (net (code "105") (name "/SDRAM_DQ24") (class "Default")
      (node (ref "U10") (pin "109") (pinfunction "IO,_DIFFIO_B20n_109") (pintype "bidirectional"))
      (node (ref "U12") (pin "45") (pinfunction "DQ24_45") (pintype "bidirectional"))
    )
    (net (code "106") (name "/SDRAM_DQ25") (class "Default")
      (node (ref "U10") (pin "108") (pinfunction "IO,_DIFFIO_B20p_108") (pintype "bidirectional"))
      (node (ref "U12") (pin "47") (pinfunction "DQ25_47") (pintype "bidirectional"))
    )
    (net (code "107") (name "/SDRAM_DQ26") (class "Default")
      (node (ref "U10") (pin "106") (pinfunction "IO,_(DQS2B/CQ3B,DPCLK5)_106") (pintype "bidirectional"))
      (node (ref "U12") (pin "48") (pinfunction "DQ26_48") (pintype "bidirectional"))
    )
    (net (code "108") (name "/SDRAM_DQ27") (class "Default")
      (node (ref "U10") (pin "103") (pinfunction "IO,_(DQ5B)_103") (pintype "bidirectional"))
      (node (ref "U12") (pin "50") (pinfunction "DQ27_50") (pintype "bidirectional"))
    )
    (net (code "109") (name "/SDRAM_DQ28") (class "Default")
      (node (ref "U10") (pin "100") (pinfunction "IO,_(DQ5B)_100") (pintype "bidirectional"))
      (node (ref "U12") (pin "51") (pinfunction "DQ28_51") (pintype "bidirectional"))
    )
    (net (code "110") (name "/SDRAM_DQ29") (class "Default")
      (node (ref "U10") (pin "99") (pinfunction "IO,_DIFFIO_B16n,_(DQS4B/CQ5B,DPCLK4)_99") (pintype "bidirectional"))
      (node (ref "U12") (pin "53") (pinfunction "DQ29_53") (pintype "bidirectional"))
    )
    (net (code "111") (name "/SDRAM_DQ30") (class "Default")
      (node (ref "U10") (pin "98") (pinfunction "IO,_DIFFIO_B16p,_(DQ5B)_98") (pintype "bidirectional"))
      (node (ref "U12") (pin "54") (pinfunction "DQ30_54") (pintype "bidirectional"))
    )
    (net (code "112") (name "/SDRAM_DQ31") (class "Default")
      (node (ref "U10") (pin "95") (pinfunction "IO_95") (pintype "bidirectional"))
      (node (ref "U12") (pin "56") (pinfunction "DQ31_56") (pintype "bidirectional"))
    )
    (net (code "113") (name "/SDRAM_DQM0") (class "Default")
      (node (ref "U10") (pin "50") (pinfunction "IO,_DIFFIO_L13n_50") (pintype "bidirectional"))
      (node (ref "U12") (pin "16") (pinfunction "DQM0_16") (pintype "input"))
    )
    (net (code "114") (name "/SDRAM_DQM1") (class "Default")
      (node (ref "U10") (pin "73") (pinfunction "IO_73") (pintype "bidirectional"))
      (node (ref "U12") (pin "71") (pinfunction "DQM1_71") (pintype "input"))
    )
    (net (code "115") (name "/SDRAM_DQM2") (class "Default")
      (node (ref "U10") (pin "118") (pinfunction "IO,_PLL4_CLKOUTn_118") (pintype "bidirectional"))
      (node (ref "U12") (pin "28") (pinfunction "DQM2_28") (pintype "input"))
    )
    (net (code "116") (name "/SDRAM_DQM3") (class "Default")
      (node (ref "U10") (pin "94") (pinfunction "IO,_DIFFIO_B13n,_(DQ5B)_94") (pintype "bidirectional"))
      (node (ref "U12") (pin "59") (pinfunction "DQM3_59") (pintype "input"))
    )
    (net (code "117") (name "/SDRAM_nCAS") (class "Default")
      (node (ref "U10") (pin "52") (pinfunction "IO,_RDN1,_(DQ1L)_52") (pintype "bidirectional"))
      (node (ref "U12") (pin "18") (pinfunction "CAS#_18") (pintype "input"))
    )
    (net (code "118") (name "/SDRAM_nCS") (class "Default")
      (node (ref "U10") (pin "56") (pinfunction "IO,_DIFFIO_L15p_56") (pintype "bidirectional"))
      (node (ref "U12") (pin "20") (pinfunction "CS#_20") (pintype "input"))
    )
    (net (code "119") (name "/SDRAM_nRAS") (class "Default")
      (node (ref "U10") (pin "55") (pinfunction "IO,_(DQS3L/CQ3L#,CDPCLK1)_55") (pintype "bidirectional"))
      (node (ref "U12") (pin "19") (pinfunction "RAS#_19") (pintype "input"))
    )
    (net (code "120") (name "/SDRAM_nWE") (class "Default")
      (node (ref "U10") (pin "51") (pinfunction "IO,_RUP1,_(DQ1L)_51") (pintype "bidirectional"))
      (node (ref "U12") (pin "17") (pinfunction "WE#_17") (pintype "input"))
    )
    (net (code "121") (name "/USBDM") (class "Default")
      (node (ref "J2") (pin "2") (pinfunction "D-_2") (pintype "passive"))
      (node (ref "U5") (pin "16") (pinfunction "USBDM_16") (pintype "bidirectional"))
    )
    (net (code "122") (name "/USBDP") (class "Default")
      (node (ref "J2") (pin "3") (pinfunction "D+_3") (pintype "passive"))
      (node (ref "U5") (pin "15") (pinfunction "USBDP_15") (pintype "bidirectional"))
    )
    (net (code "123") (name "/USER_FLASH_CLK") (class "Default")
      (node (ref "U10") (pin "239") (pinfunction "IO,_PLL3_CLKOUTn_239") (pintype "bidirectional"))
      (node (ref "U4") (pin "6") (pinfunction "C_6") (pintype "input"))
    )
    (net (code "124") (name "/USER_FLASH_CS") (class "Default")
      (node (ref "U10") (pin "6") (pinfunction "IO_6") (pintype "bidirectional"))
      (node (ref "U4") (pin "1") (pinfunction "S#_1") (pintype "input"))
    )
    (net (code "125") (name "/USER_FLASH_DQ0") (class "Default")
      (node (ref "U10") (pin "240") (pinfunction "IO,_PLL3_CLKOUTp_240") (pintype "bidirectional"))
      (node (ref "U4") (pin "5") (pinfunction "DQ0_5") (pintype "input"))
    )
    (net (code "126") (name "/USER_FLASH_DQ1") (class "Default")
      (node (ref "U10") (pin "5") (pinfunction "IO,_DIFFIO_L1n_5") (pintype "bidirectional"))
      (node (ref "U4") (pin "2") (pinfunction "DQ1_2") (pintype "tri_state"))
    )
    (net (code "127") (name "/USER_FLASH_DQ2") (class "Default")
      (node (ref "U10") (pin "4") (pinfunction "IO,_DIFFIO_L1p_4") (pintype "bidirectional"))
      (node (ref "U4") (pin "3") (pinfunction "W#_3") (pintype "input"))
    )
    (net (code "128") (name "/USER_FLASH_DQ3") (class "Default")
      (node (ref "U10") (pin "238") (pinfunction "IO,_DIFFIO_T1p_238") (pintype "bidirectional"))
      (node (ref "U4") (pin "7") (pinfunction "HOLD#_7") (pintype "input"))
    )
    (net (code "129") (name "/VGA_B") (class "Default")
      (node (ref "1") (pin "3") (pinfunction "3_3") (pintype "passive"))
      (node (ref "R52") (pin "2") (pinfunction "2_2") (pintype "passive"))
      (node (ref "R53") (pin "2") (pinfunction "2_2") (pintype "passive"))
      (node (ref "R54") (pin "2") (pinfunction "2_2") (pintype "passive"))
    )
    (net (code "130") (name "/VGA_G") (class "Default")
      (node (ref "1") (pin "2") (pinfunction "2_2") (pintype "passive"))
      (node (ref "R43") (pin "2") (pinfunction "2_2") (pintype "passive"))
      (node (ref "R44") (pin "2") (pinfunction "2_2") (pintype "passive"))
      (node (ref "R48") (pin "2") (pinfunction "2_2") (pintype "passive"))
    )
    (net (code "131") (name "/VGA_HSYNC") (class "Default")
      (node (ref "1") (pin "13") (pinfunction "13_13") (pintype "passive"))
      (node (ref "R37") (pin "1") (pinfunction "1_1") (pintype "passive"))
    )
    (net (code "132") (name "/VGA_R") (class "Default")
      (node (ref "1") (pin "1") (pinfunction "1_1") (pintype "passive"))
      (node (ref "R38") (pin "2") (pinfunction "2_2") (pintype "passive"))
      (node (ref "R40") (pin "2") (pinfunction "2_2") (pintype "passive"))
      (node (ref "R42") (pin "2") (pinfunction "2_2") (pintype "passive"))
    )
    (net (code "133") (name "/VGA_VSYNC") (class "Default")
      (node (ref "1") (pin "14") (pinfunction "14_14") (pintype "passive"))
      (node (ref "R34") (pin "1") (pinfunction "1_1") (pintype "passive"))
    )
    (net (code "134") (name "/WIFI_CH_PD") (class "Default")
      (node (ref "P3") (pin "6") (pinfunction "6_6") (pintype "passive"))
      (node (ref "R25") (pin "1") (pinfunction "1_1") (pintype "passive"))
    )
    (net (code "135") (name "/WIFI_GPIO0") (class "Default")
      (node (ref "P3") (pin "3") (pinfunction "3_3") (pintype "passive"))
      (node (ref "R28") (pin "1") (pinfunction "1_1") (pintype "passive"))
      (node (ref "R30") (pin "2") (pinfunction "2_2") (pintype "passive"))
    )
    (net (code "136") (name "/WIFI_GPIO2") (class "Default")
      (node (ref "P3") (pin "5") (pinfunction "5_5") (pintype "passive"))
      (node (ref "R27") (pin "1") (pinfunction "1_1") (pintype "passive"))
    )
    (net (code "137") (name "/WIFI_RESET") (class "Default")
      (node (ref "P3") (pin "4") (pinfunction "4_4") (pintype "passive"))
      (node (ref "R26") (pin "1") (pinfunction "1_1") (pintype "passive"))
      (node (ref "U10") (pin "200") (pinfunction "IO,_(PADD4),_(DQS2T/CQ3T,DPCLK8)_200") (pintype "bidirectional"))
    )
    (net (code "138") (name "/WIFI_RXD") (class "Default")
      (node (ref "P3") (pin "1") (pinfunction "1_1") (pintype "passive"))
      (node (ref "U10") (pin "201") (pinfunction "IO,_(PADD5),_(DQ5T)_201") (pintype "bidirectional"))
    )
    (net (code "139") (name "/WIFI_TXD") (class "Default")
      (node (ref "P3") (pin "8") (pinfunction "8_8") (pintype "passive"))
      (node (ref "U10") (pin "197") (pinfunction "IO,_DIFFIO_T19p,_(PADD2),_(DQ5T)_197") (pintype "bidirectional"))
    )
    (net (code "140") (name "/nCE") (class "Default")
      (node (ref "R55") (pin "1") (pinfunction "1_1") (pintype "passive"))
      (node (ref "U10") (pin "30") (pinfunction "nCE_30") (pintype "input"))
    )
    (net (code "141") (name "/nCONFIG") (class "Default")
      (node (ref "R56") (pin "2") (pinfunction "2_2") (pintype "passive"))
      (node (ref "U10") (pin "25") (pinfunction "nCONFIG_25") (pintype "input"))
    )
    (net (code "142") (name "/nCSO") (class "Default")
      (node (ref "U10") (pin "14") (pinfunction "IO,_(FLASH_nCE,_nCSO)_14") (pintype "bidirectional"))
      (node (ref "U11") (pin "1") (pinfunction "S#_1") (pintype "input"))
    )
    (net (code "143") (name "/nSTATUS") (class "Default")
      (node (ref "R57") (pin "2") (pinfunction "2_2") (pintype "passive"))
      (node (ref "U10") (pin "17") (pinfunction "nSTATUS_17") (pintype "bidirectional"))
    )
    (net (code "144") (name "1.2V") (class "Default")
      (node (ref "C26") (pin "2") (pinfunction "2_2") (pintype "passive"))
      (node (ref "C27") (pin "2") (pinfunction "2_2") (pintype "passive"))
      (node (ref "C28") (pin "2") (pinfunction "2_2") (pintype "passive"))
      (node (ref "C29") (pin "2") (pinfunction "2_2") (pintype "passive"))
      (node (ref "C30") (pin "2") (pinfunction "2_2") (pintype "passive"))
      (node (ref "C31") (pin "2") (pinfunction "2_2") (pintype "passive"))
      (node (ref "C32") (pin "2") (pinfunction "2_2") (pintype "passive"))
      (node (ref "C33") (pin "2") (pinfunction "2_2") (pintype "passive"))
      (node (ref "C34") (pin "2") (pinfunction "2_2") (pintype "passive"))
      (node (ref "C35") (pin "2") (pinfunction "2_2") (pintype "passive"))
      (node (ref "C36") (pin "2") (pinfunction "2_2") (pintype "passive"))
      (node (ref "C37") (pin "2") (pinfunction "2_2") (pintype "passive"))
      (node (ref "C38") (pin "2") (pinfunction "2_2") (pintype "passive"))
      (node (ref "C39") (pin "2") (pinfunction "2_2") (pintype "passive"))
      (node (ref "C4") (pin "1") (pinfunction "1_1") (pintype "passive"))
      (node (ref "C40") (pin "2") (pinfunction "2_2") (pintype "passive"))
      (node (ref "C41") (pin "2") (pinfunction "2_2") (pintype "passive"))
      (node (ref "C42") (pin "2") (pinfunction "2_2") (pintype "passive"))
      (node (ref "C67") (pin "2") (pinfunction "2_2") (pintype "passive"))
      (node (ref "C68") (pin "2") (pinfunction "2_2") (pintype "passive"))
      (node (ref "C69") (pin "2") (pinfunction "2_2") (pintype "passive"))
      (node (ref "D4") (pin "1") (pinfunction "A_1") (pintype "passive"))
      (node (ref "P1") (pin "4") (pinfunction "4_4") (pintype "passive"))
      (node (ref "U10") (pin "1") (pinfunction "VCCD_PLL3_1") (pintype "power_in"))
      (node (ref "U10") (pin "10") (pinfunction "VCCINT_10") (pintype "power_in"))
      (node (ref "U10") (pin "101") (pinfunction "VCCINT_101") (pintype "power_in"))
      (node (ref "U10") (pin "115") (pinfunction "VCCINT_115") (pintype "power_in"))
      (node (ref "U10") (pin "121") (pinfunction "VCCD_PLL4_121") (pintype "power_in"))
      (node (ref "U10") (pin "129") (pinfunction "VCCINT_129") (pintype "power_in"))
      (node (ref "U10") (pin "140") (pinfunction "VCCINT_140") (pintype "power_in"))
      (node (ref "U10") (pin "163") (pinfunction "VCCINT_163") (pintype "power_in"))
      (node (ref "U10") (pin "174") (pinfunction "VCCINT_174") (pintype "power_in"))
      (node (ref "U10") (pin "180") (pinfunction "VCCD_PLL2_180") (pintype "power_in"))
      (node (ref "U10") (pin "19") (pinfunction "VCCINT_19") (pintype "power_in"))
      (node (ref "U10") (pin "190") (pinfunction "VCCINT_190") (pintype "power_in"))
      (node (ref "U10") (pin "198") (pinfunction "VCCINT_198") (pintype "power_in"))
      (node (ref "U10") (pin "204") (pinfunction "VCCINT_204") (pintype "power_in"))
      (node (ref "U10") (pin "220") (pinfunction "VCCINT_220") (pintype "power_in"))
      (node (ref "U10") (pin "228") (pinfunction "VCCINT_228") (pintype "power_in"))
      (node (ref "U10") (pin "40") (pinfunction "VCCINT_40") (pintype "power_in"))
      (node (ref "U10") (pin "53") (pinfunction "VCCINT_53") (pintype "power_in"))
      (node (ref "U10") (pin "60") (pinfunction "VCCD_PLL1_60") (pintype "power_in"))
      (node (ref "U10") (pin "61") (pinfunction "VCCINT_61") (pintype "power_in"))
      (node (ref "U10") (pin "74") (pinfunction "VCCINT_74") (pintype "power_in"))
      (node (ref "U10") (pin "85") (pinfunction "VCCINT_85") (pintype "power_in"))
      (node (ref "U2") (pin "2") (pinfunction "Vout_2") (pintype "passive"))
    )
    (net (code "145") (name "2.5V") (class "Default")
      (node (ref "C3") (pin "1") (pinfunction "1_1") (pintype "passive"))
      (node (ref "C57") (pin "2") (pinfunction "2_2") (pintype "passive"))
      (node (ref "C58") (pin "2") (pinfunction "2_2") (pintype "passive"))
      (node (ref "C59") (pin "2") (pinfunction "2_2") (pintype "passive"))
      (node (ref "C60") (pin "2") (pinfunction "2_2") (pintype "passive"))
      (node (ref "D3") (pin "1") (pinfunction "A_1") (pintype "passive"))
      (node (ref "P1") (pin "3") (pinfunction "3_3") (pintype "passive"))
      (node (ref "R39") (pin "2") (pinfunction "2_2") (pintype "passive"))
      (node (ref "R4") (pin "2") (pinfunction "2_2") (pintype "passive"))
      (node (ref "R45") (pin "2") (pinfunction "2_2") (pintype "passive"))
      (node (ref "R46") (pin "2") (pinfunction "2_2") (pintype "passive"))
      (node (ref "R47") (pin "2") (pinfunction "2_2") (pintype "passive"))
      (node (ref "U1") (pin "2") (pinfunction "Vout_2") (pintype "passive"))
      (node (ref "U10") (pin "123") (pinfunction "VCCA4_123") (pintype "power_in"))
      (node (ref "U10") (pin "178") (pinfunction "VCCA2_178") (pintype "power_in"))
      (node (ref "U10") (pin "3") (pinfunction "VCCA3_3") (pintype "power_in"))
      (node (ref "U10") (pin "58") (pinfunction "VCCA1_58") (pintype "power_in"))
      (node (ref "U2") (pin "3") (pinfunction "Vin_3") (pintype "passive"))
    )
    (net (code "146") (name "3V") (class "Default")
      (node (ref "C13") (pin "2") (pinfunction "2_2") (pintype "passive"))
      (node (ref "C14") (pin "2") (pinfunction "2_2") (pintype "passive"))
      (node (ref "C15") (pin "2") (pinfunction "2_2") (pintype "passive"))
      (node (ref "C16") (pin "2") (pinfunction "2_2") (pintype "passive"))
      (node (ref "C17") (pin "2") (pinfunction "2_2") (pintype "passive"))
      (node (ref "C18") (pin "2") (pinfunction "2_2") (pintype "passive"))
      (node (ref "C19") (pin "2") (pinfunction "2_2") (pintype "passive"))
      (node (ref "C2") (pin "1") (pinfunction "1_1") (pintype "passive"))
      (node (ref "C20") (pin "2") (pinfunction "2_2") (pintype "passive"))
      (node (ref "C21") (pin "2") (pinfunction "2_2") (pintype "passive"))
      (node (ref "C22") (pin "2") (pinfunction "2_2") (pintype "passive"))
      (node (ref "C23") (pin "2") (pinfunction "2_2") (pintype "passive"))
      (node (ref "C24") (pin "2") (pinfunction "2_2") (pintype "passive"))
      (node (ref "C25") (pin "2") (pinfunction "2_2") (pintype "passive"))
      (node (ref "C43") (pin "2") (pinfunction "2_2") (pintype "passive"))
      (node (ref "C44") (pin "2") (pinfunction "2_2") (pintype "passive"))
      (node (ref "C45") (pin "2") (pinfunction "2_2") (pintype "passive"))
      (node (ref "C46") (pin "2") (pinfunction "2_2") (pintype "passive"))
      (node (ref "C47") (pin "2") (pinfunction "2_2") (pintype "passive"))
      (node (ref "C48") (pin "2") (pinfunction "2_2") (pintype "passive"))
      (node (ref "C49") (pin "2") (pinfunction "2_2") (pintype "passive"))
      (node (ref "C50") (pin "2") (pinfunction "2_2") (pintype "passive"))
      (node (ref "C51") (pin "2") (pinfunction "2_2") (pintype "passive"))
      (node (ref "C52") (pin "2") (pinfunction "2_2") (pintype "passive"))
      (node (ref "C53") (pin "2") (pinfunction "2_2") (pintype "passive"))
      (node (ref "C54") (pin "2") (pinfunction "2_2") (pintype "passive"))
      (node (ref "C55") (pin "2") (pinfunction "2_2") (pintype "passive"))
      (node (ref "C56") (pin "2") (pinfunction "2_2") (pintype "passive"))
      (node (ref "C6") (pin "2") (pinfunction "2_2") (pintype "passive"))
      (node (ref "C61") (pin "2") (pinfunction "2_2") (pintype "passive"))
      (node (ref "C62") (pin "2") (pinfunction "2_2") (pintype "passive"))
      (node (ref "C63") (pin "2") (pinfunction "2_2") (pintype "passive"))
      (node (ref "C64") (pin "2") (pinfunction "2_2") (pintype "passive"))
      (node (ref "C65") (pin "2") (pinfunction "2_2") (pintype "passive"))
      (node (ref "C66") (pin "2") (pinfunction "2_2") (pintype "passive"))
      (node (ref "C8") (pin "1") (pinfunction "1_1") (pintype "passive"))
      (node (ref "C9") (pin "2") (pinfunction "2_2") (pintype "passive"))
      (node (ref "D2") (pin "1") (pinfunction "A_1") (pintype "passive"))
      (node (ref "D5") (pin "2") (pintype "passive"))
      (node (ref "D6") (pin "2") (pintype "passive"))
      (node (ref "D7") (pin "2") (pintype "passive"))
      (node (ref "D8") (pin "2") (pintype "passive"))
      (node (ref "J4") (pin "4") (pinfunction "4_4") (pintype "bidirectional"))
      (node (ref "P1") (pin "2") (pinfunction "2_2") (pintype "passive"))
      (node (ref "P2") (pin "17") (pinfunction "17_17") (pintype "passive"))
      (node (ref "P3") (pin "2") (pinfunction "2_2") (pintype "passive"))
      (node (ref "P4") (pin "9") (pinfunction "9_9") (pintype "passive"))
      (node (ref "R13") (pin "2") (pinfunction "2_2") (pintype "passive"))
      (node (ref "R14") (pin "1") (pinfunction "1_1") (pintype "passive"))
      (node (ref "R15") (pin "2") (pinfunction "2_2") (pintype "passive"))
      (node (ref "R17") (pin "2") (pinfunction "2_2") (pintype "passive"))
      (node (ref "R19") (pin "2") (pinfunction "2_2") (pintype "passive"))
      (node (ref "R22") (pin "2") (pinfunction "2_2") (pintype "passive"))
      (node (ref "R25") (pin "2") (pinfunction "2_2") (pintype "passive"))
      (node (ref "R26") (pin "2") (pinfunction "2_2") (pintype "passive"))
      (node (ref "R27") (pin "2") (pinfunction "2_2") (pintype "passive"))
      (node (ref "R28") (pin "2") (pinfunction "2_2") (pintype "passive"))
      (node (ref "R31") (pin "2") (pinfunction "2_2") (pintype "passive"))
      (node (ref "R41") (pin "2") (pinfunction "2_2") (pintype "passive"))
      (node (ref "R5") (pin "2") (pinfunction "2_2") (pintype "passive"))
      (node (ref "R56") (pin "1") (pinfunction "1_1") (pintype "passive"))
      (node (ref "R57") (pin "1") (pinfunction "1_1") (pintype "passive"))
      (node (ref "R58") (pin "1") (pinfunction "1_1") (pintype "passive"))
      (node (ref "R60") (pin "1") (pinfunction "1_1") (pintype "passive"))
      (node (ref "U10") (pin "104") (pinfunction "VCCIO4_104") (pintype "power_in"))
      (node (ref "U10") (pin "124") (pinfunction "VCCIO5_124") (pintype "power_in"))
      (node (ref "U10") (pin "136") (pinfunction "VCCIO5_136") (pintype "power_in"))
      (node (ref "U10") (pin "15") (pinfunction "VCCIO1_15") (pintype "power_in"))
      (node (ref "U10") (pin "154") (pinfunction "VCCIO6_154") (pintype "power_in"))
      (node (ref "U10") (pin "170") (pinfunction "VCCIO6_170") (pintype "power_in"))
      (node (ref "U10") (pin "192") (pinfunction "VCCIO7_192") (pintype "power_in"))
      (node (ref "U10") (pin "206") (pinfunction "VCCIO7_206") (pintype "power_in"))
      (node (ref "U10") (pin "213") (pinfunction "VCCIO8_213") (pintype "power_in"))
      (node (ref "U10") (pin "225") (pinfunction "VCCIO8_225") (pintype "power_in"))
      (node (ref "U10") (pin "35") (pinfunction "VCCIO2_35") (pintype "power_in"))
      (node (ref "U10") (pin "47") (pinfunction "VCCIO2_47") (pintype "power_in"))
      (node (ref "U10") (pin "66") (pinfunction "VCCIO3_66") (pintype "power_in"))
      (node (ref "U10") (pin "7") (pinfunction "VCCIO1_7") (pintype "power_in"))
      (node (ref "U10") (pin "77") (pinfunction "VCCIO3_77") (pintype "power_in"))
      (node (ref "U10") (pin "96") (pinfunction "VCCIO4_96") (pintype "power_in"))
      (node (ref "U11") (pin "8") (pinfunction "VCC_8") (pintype "power_in"))
      (node (ref "U12") (pin "1") (pinfunction "VDD_1") (pintype "power_in"))
      (node (ref "U12") (pin "15") (pinfunction "VDD_15") (pintype "power_in"))
      (node (ref "U12") (pin "29") (pinfunction "VDD_29") (pintype "power_in"))
      (node (ref "U12") (pin "3") (pinfunction "VDDQ_3") (pintype "power_in"))
      (node (ref "U12") (pin "35") (pinfunction "VDDQ_35") (pintype "power_in"))
      (node (ref "U12") (pin "41") (pinfunction "VDDQ_41") (pintype "power_in"))
      (node (ref "U12") (pin "43") (pinfunction "VDD_43") (pintype "power_in"))
      (node (ref "U12") (pin "49") (pinfunction "VDDQ_49") (pintype "power_in"))
      (node (ref "U12") (pin "55") (pinfunction "VDDQ_55") (pintype "power_in"))
      (node (ref "U12") (pin "75") (pinfunction "VDDQ_75") (pintype "power_in"))
      (node (ref "U12") (pin "81") (pinfunction "VDDQ_81") (pintype "power_in"))
      (node (ref "U12") (pin "9") (pinfunction "VDDQ_9") (pintype "power_in"))
      (node (ref "U3") (pin "2") (pinfunction "Vout_2") (pintype "passive"))
      (node (ref "U4") (pin "8") (pinfunction "VCC_8") (pintype "power_in"))
      (node (ref "U5") (pin "4") (pinfunction "VCCIO_4") (pintype "power_in"))
      (node (ref "U6") (pin "1") (pinfunction "G_1") (pintype "passive"))
      (node (ref "U7") (pin "1") (pinfunction "G_1") (pintype "passive"))
      (node (ref "U8") (pin "1") (pinfunction "G_1") (pintype "passive"))
      (node (ref "U9") (pin "1") (pinfunction "G_1") (pintype "passive"))
      (node (ref "Y1") (pin "4") (pinfunction "VDD_4") (pintype "power_in"))
    )
    (net (code "147") (name "5V") (class "Default")
      (node (ref "C1") (pin "1") (pinfunction "1_1") (pintype "passive"))
      (node (ref "C12") (pin "2") (pinfunction "2_2") (pintype "passive"))
      (node (ref "C7") (pin "1") (pinfunction "1_1") (pintype "passive"))
      (node (ref "D1") (pin "1") (pinfunction "A_1") (pintype "passive"))
      (node (ref "J1") (pin "4") (pinfunction "VCC_4") (pintype "power_in"))
      (node (ref "J2") (pin "1") (pinfunction "VCC_1") (pintype "passive"))
      (node (ref "J3") (pin "4") (pinfunction "VCC_4") (pintype "power_in"))
      (node (ref "P1") (pin "1") (pinfunction "1_1") (pintype "passive"))
      (node (ref "P2") (pin "18") (pinfunction "18_18") (pintype "passive"))
      (node (ref "R16") (pin "2") (pinfunction "2_2") (pintype "passive"))
      (node (ref "R18") (pin "2") (pinfunction "2_2") (pintype "passive"))
      (node (ref "R20") (pin "2") (pinfunction "2_2") (pintype "passive"))
      (node (ref "R23") (pin "2") (pinfunction "2_2") (pintype "passive"))
      (node (ref "U1") (pin "3") (pinfunction "Vin_3") (pintype "passive"))
      (node (ref "U3") (pin "3") (pinfunction "Vin_3") (pintype "passive"))
      (node (ref "U5") (pin "20") (pinfunction "VCC_20") (pintype "power_in"))
    )
    (net (code "148") (name "GND") (class "Default")
      (node (ref "1") (pin "10") (pinfunction "10_10") (pintype "passive"))
      (node (ref "1") (pin "5") (pinfunction "5_5") (pintype "passive"))
      (node (ref "1") (pin "6") (pinfunction "6_6") (pintype "passive"))
      (node (ref "1") (pin "7") (pinfunction "7_7") (pintype "passive"))
      (node (ref "1") (pin "8") (pinfunction "8_8") (pintype "passive"))
      (node (ref "C1") (pin "2") (pinfunction "2_2") (pintype "passive"))
      (node (ref "C10") (pin "1") (pinfunction "1_1") (pintype "passive"))
      (node (ref "C11") (pin "1") (pinfunction "1_1") (pintype "passive"))
      (node (ref "C12") (pin "1") (pinfunction "1_1") (pintype "passive"))
      (node (ref "C13") (pin "1") (pinfunction "1_1") (pintype "passive"))
      (node (ref "C14") (pin "1") (pinfunction "1_1") (pintype "passive"))
      (node (ref "C15") (pin "1") (pinfunction "1_1") (pintype "passive"))
      (node (ref "C16") (pin "1") (pinfunction "1_1") (pintype "passive"))
      (node (ref "C17") (pin "1") (pinfunction "1_1") (pintype "passive"))
      (node (ref "C18") (pin "1") (pinfunction "1_1") (pintype "passive"))
      (node (ref "C19") (pin "1") (pinfunction "1_1") (pintype "passive"))
      (node (ref "C2") (pin "2") (pinfunction "2_2") (pintype "passive"))
      (node (ref "C20") (pin "1") (pinfunction "1_1") (pintype "passive"))
      (node (ref "C21") (pin "1") (pinfunction "1_1") (pintype "passive"))
      (node (ref "C22") (pin "1") (pinfunction "1_1") (pintype "passive"))
      (node (ref "C23") (pin "1") (pinfunction "1_1") (pintype "passive"))
      (node (ref "C24") (pin "1") (pinfunction "1_1") (pintype "passive"))
      (node (ref "C25") (pin "1") (pinfunction "1_1") (pintype "passive"))
      (node (ref "C26") (pin "1") (pinfunction "1_1") (pintype "passive"))
      (node (ref "C27") (pin "1") (pinfunction "1_1") (pintype "passive"))
      (node (ref "C28") (pin "1") (pinfunction "1_1") (pintype "passive"))
      (node (ref "C29") (pin "1") (pinfunction "1_1") (pintype "passive"))
      (node (ref "C3") (pin "2") (pinfunction "2_2") (pintype "passive"))
      (node (ref "C30") (pin "1") (pinfunction "1_1") (pintype "passive"))
      (node (ref "C31") (pin "1") (pinfunction "1_1") (pintype "passive"))
      (node (ref "C32") (pin "1") (pinfunction "1_1") (pintype "passive"))
      (node (ref "C33") (pin "1") (pinfunction "1_1") (pintype "passive"))
      (node (ref "C34") (pin "1") (pinfunction "1_1") (pintype "passive"))
      (node (ref "C35") (pin "1") (pinfunction "1_1") (pintype "passive"))
      (node (ref "C36") (pin "1") (pinfunction "1_1") (pintype "passive"))
      (node (ref "C37") (pin "1") (pinfunction "1_1") (pintype "passive"))
      (node (ref "C38") (pin "1") (pinfunction "1_1") (pintype "passive"))
      (node (ref "C39") (pin "1") (pinfunction "1_1") (pintype "passive"))
      (node (ref "C4") (pin "2") (pinfunction "2_2") (pintype "passive"))
      (node (ref "C40") (pin "1") (pinfunction "1_1") (pintype "passive"))
      (node (ref "C41") (pin "1") (pinfunction "1_1") (pintype "passive"))
      (node (ref "C42") (pin "1") (pinfunction "1_1") (pintype "passive"))
      (node (ref "C43") (pin "1") (pinfunction "1_1") (pintype "passive"))
      (node (ref "C44") (pin "1") (pinfunction "1_1") (pintype "passive"))
      (node (ref "C45") (pin "1") (pinfunction "1_1") (pintype "passive"))
      (node (ref "C46") (pin "1") (pinfunction "1_1") (pintype "passive"))
      (node (ref "C47") (pin "1") (pinfunction "1_1") (pintype "passive"))
      (node (ref "C48") (pin "1") (pinfunction "1_1") (pintype "passive"))
      (node (ref "C49") (pin "1") (pinfunction "1_1") (pintype "passive"))
      (node (ref "C5") (pin "2") (pinfunction "2_2") (pintype "passive"))
      (node (ref "C50") (pin "1") (pinfunction "1_1") (pintype "passive"))
      (node (ref "C51") (pin "1") (pinfunction "1_1") (pintype "passive"))
      (node (ref "C52") (pin "1") (pinfunction "1_1") (pintype "passive"))
      (node (ref "C53") (pin "1") (pinfunction "1_1") (pintype "passive"))
      (node (ref "C54") (pin "1") (pinfunction "1_1") (pintype "passive"))
      (node (ref "C55") (pin "1") (pinfunction "1_1") (pintype "passive"))
      (node (ref "C56") (pin "1") (pinfunction "1_1") (pintype "passive"))
      (node (ref "C57") (pin "1") (pinfunction "1_1") (pintype "passive"))
      (node (ref "C58") (pin "1") (pinfunction "1_1") (pintype "passive"))
      (node (ref "C59") (pin "1") (pinfunction "1_1") (pintype "passive"))
      (node (ref "C6") (pin "1") (pinfunction "1_1") (pintype "passive"))
      (node (ref "C60") (pin "1") (pinfunction "1_1") (pintype "passive"))
      (node (ref "C61") (pin "1") (pinfunction "1_1") (pintype "passive"))
      (node (ref "C62") (pin "1") (pinfunction "1_1") (pintype "passive"))
      (node (ref "C63") (pin "1") (pinfunction "1_1") (pintype "passive"))
      (node (ref "C64") (pin "1") (pinfunction "1_1") (pintype "passive"))
      (node (ref "C65") (pin "1") (pinfunction "1_1") (pintype "passive"))
      (node (ref "C66") (pin "1") (pinfunction "1_1") (pintype "passive"))
      (node (ref "C67") (pin "1") (pinfunction "1_1") (pintype "passive"))
      (node (ref "C68") (pin "1") (pinfunction "1_1") (pintype "passive"))
      (node (ref "C69") (pin "1") (pinfunction "1_1") (pintype "passive"))
      (node (ref "C7") (pin "2") (pinfunction "2_2") (pintype "passive"))
      (node (ref "C8") (pin "2") (pinfunction "2_2") (pintype "passive"))
      (node (ref "C9") (pin "1") (pinfunction "1_1") (pintype "passive"))
      (node (ref "J1") (pin "0") (pinfunction "Shield_0") (pintype "passive"))
      (node (ref "J1") (pin "3") (pinfunction "GND_3") (pintype "power_in"))
      (node (ref "J2") (pin "5") (pinfunction "GND_5") (pintype "passive"))
      (node (ref "J2") (pin "S") (pinfunction "Shield_S") (pintype "passive"))
      (node (ref "J3") (pin "0") (pinfunction "Shield_0") (pintype "passive"))
      (node (ref "J3") (pin "3") (pinfunction "GND_3") (pintype "power_in"))
      (node (ref "J4") (pin "6") (pinfunction "6_6") (pintype "bidirectional"))
      (node (ref "J5") (pin "10") (pinfunction "10_10") (pintype "passive"))
      (node (ref "J5") (pin "2") (pinfunction "2_2") (pintype "passive"))
      (node (ref "P1") (pin "5") (pinfunction "5_5") (pintype "passive"))
      (node (ref "P2") (pin "13") (pinfunction "13_13") (pintype "passive"))
      (node (ref "P2") (pin "16") (pinfunction "16_16") (pintype "passive"))
      (node (ref "P3") (pin "7") (pinfunction "7_7") (pintype "passive"))
      (node (ref "P4") (pin "10") (pinfunction "10_10") (pintype "passive"))
      (node (ref "R1") (pin "1") (pinfunction "1_1") (pintype "passive"))
      (node (ref "R2") (pin "1") (pinfunction "1_1") (pintype "passive"))
      (node (ref "R21") (pin "1") (pinfunction "1_1") (pintype "passive"))
      (node (ref "R24") (pin "1") (pinfunction "1_1") (pintype "passive"))
      (node (ref "R3") (pin "1") (pinfunction "1_1") (pintype "passive"))
      (node (ref "R30") (pin "1") (pinfunction "1_1") (pintype "passive"))
      (node (ref "R49") (pin "1") (pinfunction "1_1") (pintype "passive"))
      (node (ref "R50") (pin "1") (pinfunction "1_1") (pintype "passive"))
      (node (ref "R51") (pin "1") (pinfunction "1_1") (pintype "passive"))
      (node (ref "R55") (pin "2") (pinfunction "2_2") (pintype "passive"))
      (node (ref "R6") (pin "1") (pinfunction "1_1") (pintype "passive"))
      (node (ref "R61") (pin "2") (pinfunction "2_2") (pintype "passive"))
      (node (ref "R7") (pin "1") (pinfunction "1_1") (pintype "passive"))
      (node (ref "R8") (pin "1") (pinfunction "1_1") (pintype "passive"))
      (node (ref "U10") (pin "102") (pinfunction "GND_102") (pintype "power_in"))
      (node (ref "U10") (pin "105") (pinfunction "GND_105") (pintype "power_in"))
      (node (ref "U10") (pin "107") (pinfunction "IO,_VREFB4N0_107") (pintype "bidirectional"))
      (node (ref "U10") (pin "11") (pinfunction "GND_11") (pintype "power_in"))
      (node (ref "U10") (pin "116") (pinfunction "GND_116") (pintype "power_in"))
      (node (ref "U10") (pin "122") (pinfunction "GNDA4_122") (pintype "power_in"))
      (node (ref "U10") (pin "125") (pinfunction "GND_125") (pintype "power_in"))
      (node (ref "U10") (pin "130") (pinfunction "GND_130") (pintype "power_in"))
      (node (ref "U10") (pin "133") (pinfunction "IO,_VREFB5N0_133") (pintype "bidirectional"))
      (node (ref "U10") (pin "138") (pinfunction "GND_138") (pintype "power_in"))
      (node (ref "U10") (pin "141") (pinfunction "GND_141") (pintype "power_in"))
      (node (ref "U10") (pin "149") (pinfunction "CLK7,_DIFFCLK_3n_149") (pintype "input"))
      (node (ref "U10") (pin "150") (pinfunction "CLK6,_DIFFCLK_3p_150") (pintype "input"))
      (node (ref "U10") (pin "151") (pinfunction "CLK5,_DIFFCLK_2n_151") (pintype "input"))
      (node (ref "U10") (pin "152") (pinfunction "CLK4,_DIFFCLK_2p_152") (pintype "input"))
      (node (ref "U10") (pin "156") (pinfunction "GND_156") (pintype "power_in"))
      (node (ref "U10") (pin "16") (pinfunction "GND_16") (pintype "power_in"))
      (node (ref "U10") (pin "165") (pinfunction "GND_165") (pintype "power_in"))
      (node (ref "U10") (pin "172") (pinfunction "GND_172") (pintype "power_in"))
      (node (ref "U10") (pin "175") (pinfunction "GND_175") (pintype "power_in"))
      (node (ref "U10") (pin "179") (pinfunction "GNDA2_179") (pintype "power_in"))
      (node (ref "U10") (pin "191") (pinfunction "GND_191") (pintype "power_in"))
      (node (ref "U10") (pin "193") (pinfunction "GND_193") (pintype "power_in"))
      (node (ref "U10") (pin "199") (pinfunction "GND_199") (pintype "power_in"))
      (node (ref "U10") (pin "2") (pinfunction "GNDA3_2") (pintype "power_in"))
      (node (ref "U10") (pin "20") (pinfunction "GND_20") (pintype "power_in"))
      (node (ref "U10") (pin "205") (pinfunction "GND_205") (pintype "power_in"))
      (node (ref "U10") (pin "208") (pinfunction "GND_208") (pintype "power_in"))
      (node (ref "U10") (pin "209") (pinfunction "CLK8,_DIFFCLK_5n_209") (pintype "input"))
      (node (ref "U10") (pin "210") (pinfunction "CLK9,_DIFFCLK_5p_210") (pintype "input"))
      (node (ref "U10") (pin "211") (pinfunction "CLK10,_DIFFCLK_4n_211") (pintype "input"))
      (node (ref "U10") (pin "212") (pinfunction "CLK11,_DIFFCLK_4p_212") (pintype "input"))
      (node (ref "U10") (pin "215") (pinfunction "GND_215") (pintype "power_in"))
      (node (ref "U10") (pin "222") (pinfunction "GND_222") (pintype "power_in"))
      (node (ref "U10") (pin "227") (pinfunction "GND_227") (pintype "power_in"))
      (node (ref "U10") (pin "229") (pinfunction "GND_229") (pintype "power_in"))
      (node (ref "U10") (pin "32") (pinfunction "CLK1,_DIFFCLK_0n_32") (pintype "input"))
      (node (ref "U10") (pin "33") (pinfunction "CLK2,_DIFFCLK_1p_33") (pintype "input"))
      (node (ref "U10") (pin "34") (pinfunction "CLK3,_DIFFCLK_1n_34") (pintype "input"))
      (node (ref "U10") (pin "36") (pinfunction "GND_36") (pintype "power_in"))
      (node (ref "U10") (pin "42") (pinfunction "GND_42") (pintype "power_in"))
      (node (ref "U10") (pin "46") (pinfunction "IO,_VREFB2N0_46") (pintype "bidirectional"))
      (node (ref "U10") (pin "48") (pinfunction "GND_48") (pintype "power_in"))
      (node (ref "U10") (pin "54") (pinfunction "GND_54") (pintype "power_in"))
      (node (ref "U10") (pin "59") (pinfunction "GNDA1_59") (pintype "power_in"))
      (node (ref "U10") (pin "62") (pinfunction "GND_62") (pintype "power_in"))
      (node (ref "U10") (pin "67") (pinfunction "GND_67") (pintype "power_in"))
      (node (ref "U10") (pin "75") (pinfunction "GND_75") (pintype "power_in"))
      (node (ref "U10") (pin "76") (pinfunction "IO,_VREFB3N0_76") (pintype "bidirectional"))
      (node (ref "U10") (pin "79") (pinfunction "GND_79") (pintype "power_in"))
      (node (ref "U10") (pin "8") (pinfunction "GND_8") (pintype "power_in"))
      (node (ref "U10") (pin "86") (pinfunction "GND_86") (pintype "power_in"))
      (node (ref "U10") (pin "89") (pinfunction "CLK15,_DIFFCLK_6p_89") (pintype "input"))
      (node (ref "U10") (pin "90") (pinfunction "CLK14,_DIFFCLK_6n_90") (pintype "input"))
      (node (ref "U10") (pin "91") (pinfunction "CLK13,_DIFFCLK_7p_91") (pintype "input"))
      (node (ref "U10") (pin "92") (pinfunction "CLK12,_DIFFCLK_7n_92") (pintype "input"))
      (node (ref "U10") (pin "97") (pinfunction "GND_97") (pintype "power_in"))
      (node (ref "U11") (pin "4") (pinfunction "VSS_4") (pintype "power_in"))
      (node (ref "U12") (pin "12") (pinfunction "VSSQ_12") (pintype "power_in"))
      (node (ref "U12") (pin "14") (pinfunction "NC_14") (pintype "passive"))
      (node (ref "U12") (pin "30") (pinfunction "NC_30") (pintype "passive"))
      (node (ref "U12") (pin "32") (pinfunction "VSSQ_32") (pintype "power_in"))
      (node (ref "U12") (pin "38") (pinfunction "VSSQ_38") (pintype "power_in"))
      (node (ref "U12") (pin "44") (pinfunction "VSS_44") (pintype "power_in"))
      (node (ref "U12") (pin "46") (pinfunction "VSSQ_46") (pintype "power_in"))
      (node (ref "U12") (pin "52") (pinfunction "VSSQ_52") (pintype "power_in"))
      (node (ref "U12") (pin "57") (pinfunction "NC_57") (pintype "passive"))
      (node (ref "U12") (pin "58") (pinfunction "VSS_58") (pintype "power_in"))
      (node (ref "U12") (pin "6") (pinfunction "VSSQ_6") (pintype "power_in"))
      (node (ref "U12") (pin "69") (pinfunction "NC_69") (pintype "passive"))
      (node (ref "U12") (pin "70") (pinfunction "NU_70") (pintype "passive"))
      (node (ref "U12") (pin "72") (pinfunction "VSS_72") (pintype "power_in"))
      (node (ref "U12") (pin "73") (pinfunction "NC_73") (pintype "passive"))
      (node (ref "U12") (pin "78") (pinfunction "VSSQ_78") (pintype "power_in"))
      (node (ref "U12") (pin "84") (pinfunction "VSSQ_84") (pintype "power_in"))
      (node (ref "U12") (pin "86") (pinfunction "VSS_86") (pintype "power_in"))
      (node (ref "U2") (pin "1") (pinfunction "GND_1") (pintype "passive"))
      (node (ref "U4") (pin "4") (pinfunction "VSS_4") (pintype "power_in"))
      (node (ref "U5") (pin "18") (pinfunction "GND_18") (pintype "power_in"))
      (node (ref "U5") (pin "21") (pinfunction "GND_21") (pintype "power_in"))
      (node (ref "U5") (pin "25") (pinfunction "AGND_25") (pintype "power_in"))
      (node (ref "U5") (pin "26") (pinfunction "TEST_26") (pintype "input"))
      (node (ref "U5") (pin "7") (pinfunction "GND_7") (pintype "power_in"))
      (node (ref "Y1") (pin "2") (pinfunction "GND_2") (pintype "power_in"))
    )
    (net (code "149") (name "Net-(D1-K)") (class "Default")
      (node (ref "D1") (pin "2") (pinfunction "K_2") (pintype "passive"))
      (node (ref "R1") (pin "2") (pinfunction "2_2") (pintype "passive"))
    )
    (net (code "150") (name "Net-(D2-K)") (class "Default")
      (node (ref "D2") (pin "2") (pinfunction "K_2") (pintype "passive"))
      (node (ref "R2") (pin "2") (pinfunction "2_2") (pintype "passive"))
    )
    (net (code "151") (name "Net-(D3-K)") (class "Default")
      (node (ref "D3") (pin "2") (pinfunction "K_2") (pintype "passive"))
      (node (ref "R3") (pin "2") (pinfunction "2_2") (pintype "passive"))
    )
    (net (code "152") (name "Net-(D4-K)") (class "Default")
      (node (ref "D4") (pin "2") (pinfunction "K_2") (pintype "passive"))
      (node (ref "R7") (pin "2") (pinfunction "2_2") (pintype "passive"))
    )
    (net (code "153") (name "Net-(D9-K)") (class "Default")
      (node (ref "D9") (pin "2") (pinfunction "K_2") (pintype "passive"))
      (node (ref "R21") (pin "2") (pinfunction "2_2") (pintype "passive"))
    )
    (net (code "154") (name "Net-(D10-K)") (class "Default")
      (node (ref "D10") (pin "2") (pinfunction "K_2") (pintype "passive"))
      (node (ref "R24") (pin "2") (pinfunction "2_2") (pintype "passive"))
    )
    (net (code "155") (name "Net-(U1-ADJ)") (class "Default")
      (node (ref "R4") (pin "1") (pinfunction "1_1") (pintype "passive"))
      (node (ref "R6") (pin "2") (pinfunction "2_2") (pintype "passive"))
      (node (ref "U1") (pin "1") (pinfunction "ADJ_1") (pintype "passive"))
    )
    (net (code "156") (name "Net-(U3-ADJ)") (class "Default")
      (node (ref "R5") (pin "1") (pinfunction "1_1") (pintype "passive"))
      (node (ref "R8") (pin "2") (pinfunction "2_2") (pintype "passive"))
      (node (ref "U3") (pin "1") (pinfunction "ADJ_1") (pintype "passive"))
    )
    (net (code "157") (name "Net-(U5-3V3OUT)") (class "Default")
      (node (ref "C5") (pin "1") (pinfunction "1_1") (pintype "passive"))
      (node (ref "U5") (pin "17") (pinfunction "3V3OUT_17") (pintype "output"))
    )
    (net (code "158") (name "Net-(U5-CBUS3)") (class "Default")
      (node (ref "R13") (pin "1") (pinfunction "1_1") (pintype "passive"))
      (node (ref "U5") (pin "14") (pinfunction "CBUS3_14") (pintype "bidirectional"))
    )
    (net (code "159") (name "Net-(U5-~{RESET})") (class "Default")
      (node (ref "R14") (pin "2") (pinfunction "2_2") (pintype "passive"))
      (node (ref "U5") (pin "19") (pinfunction "~{RESET}_19") (pintype "input"))
    )
    (net (code "160") (name "Net-(U10I-CLK0,_DIFFCLK_0p)") (class "Default")
      (node (ref "R59") (pin "1") (pinfunction "1_1") (pintype "passive"))
      (node (ref "U10") (pin "31") (pinfunction "CLK0,_DIFFCLK_0p_31") (pintype "input"))
    )
    (net (code "161") (name "Net-(U11-HOLD#)") (class "Default")
      (node (ref "R31") (pin "1") (pinfunction "1_1") (pintype "passive"))
      (node (ref "U11") (pin "3") (pinfunction "W#_3") (pintype "input"))
      (node (ref "U11") (pin "7") (pinfunction "HOLD#_7") (pintype "input"))
    )
    (net (code "162") (name "Vjtag") (class "Default")
      (node (ref "J5") (pin "4") (pinfunction "4_4") (pintype "passive"))
      (node (ref "R39") (pin "1") (pinfunction "1_1") (pintype "passive"))
      (node (ref "R41") (pin "1") (pinfunction "1_1") (pintype "passive"))
    )
    (net (code "163") (name "unconnected-(1-Pad4)") (class "Default")
      (node (ref "1") (pin "4") (pinfunction "4_4") (pintype "passive"))
    )
    (net (code "164") (name "unconnected-(1-Pad9)") (class "Default")
      (node (ref "1") (pin "9") (pinfunction "9_9") (pintype "passive"))
    )
    (net (code "165") (name "unconnected-(1-Pad11)") (class "Default")
      (node (ref "1") (pin "11") (pinfunction "11_11") (pintype "passive"))
    )
    (net (code "166") (name "unconnected-(1-Pad12)") (class "Default")
      (node (ref "1") (pin "12") (pinfunction "12_12") (pintype "passive"))
    )
    (net (code "167") (name "unconnected-(1-Pad15)") (class "Default")
      (node (ref "1") (pin "15") (pinfunction "15_15") (pintype "passive"))
    )
    (net (code "168") (name "unconnected-(D5-Pad1)") (class "Default")
      (node (ref "D5") (pin "1") (pintype "passive"))
    )
    (net (code "169") (name "unconnected-(D6-Pad1)") (class "Default")
      (node (ref "D6") (pin "1") (pintype "passive"))
    )
    (net (code "170") (name "unconnected-(D7-Pad1)") (class "Default")
      (node (ref "D7") (pin "1") (pintype "passive"))
    )
    (net (code "171") (name "unconnected-(D8-Pad1)") (class "Default")
      (node (ref "D8") (pin "1") (pintype "passive"))
    )
    (net (code "172") (name "unconnected-(J2-ID-Pad4)") (class "Default")
      (node (ref "J2") (pin "4") (pinfunction "ID_4") (pintype "passive"))
    )
    (net (code "173") (name "unconnected-(J5-Pad6)") (class "Default")
      (node (ref "J5") (pin "6") (pinfunction "6_6") (pintype "passive"))
    )
    (net (code "174") (name "unconnected-(J5-Pad7)") (class "Default")
      (node (ref "J5") (pin "7") (pinfunction "7_7") (pintype "passive"))
    )
    (net (code "175") (name "unconnected-(J5-Pad8)") (class "Default")
      (node (ref "J5") (pin "8") (pinfunction "8_8") (pintype "passive"))
    )
    (net (code "176") (name "unconnected-(P4-Pad1)") (class "Default")
      (node (ref "P4") (pin "1") (pinfunction "1_1") (pintype "passive"))
    )
    (net (code "177") (name "unconnected-(P4-Pad3)") (class "Default")
      (node (ref "P4") (pin "3") (pinfunction "3_3") (pintype "passive"))
    )
    (net (code "178") (name "unconnected-(U5-CBUS0-Pad23)") (class "Default")
      (node (ref "U5") (pin "23") (pinfunction "CBUS0_23") (pintype "bidirectional"))
    )
    (net (code "179") (name "unconnected-(U5-CBUS1-Pad22)") (class "Default")
      (node (ref "U5") (pin "22") (pinfunction "CBUS1_22") (pintype "bidirectional"))
    )
    (net (code "180") (name "unconnected-(U5-CBUS2-Pad13)") (class "Default")
      (node (ref "U5") (pin "13") (pinfunction "CBUS2_13") (pintype "bidirectional"))
    )
    (net (code "181") (name "unconnected-(U5-CBUS4-Pad12)") (class "Default")
      (node (ref "U5") (pin "12") (pinfunction "CBUS4_12") (pintype "bidirectional"))
    )
    (net (code "182") (name "unconnected-(U5-NC-Pad8)") (class "Default")
      (node (ref "U5") (pin "8") (pinfunction "NC_8") (pintype "passive"))
    )
    (net (code "183") (name "unconnected-(U5-NC-Pad24)") (class "Default")
      (node (ref "U5") (pin "24") (pinfunction "NC_24") (pintype "passive"))
    )
    (net (code "184") (name "unconnected-(U5-OSCI-Pad27)") (class "Default")
      (node (ref "U5") (pin "27") (pinfunction "OSCI_27") (pintype "input"))
    )
    (net (code "185") (name "unconnected-(U5-OSCO-Pad28)") (class "Default")
      (node (ref "U5") (pin "28") (pinfunction "OSCO_28") (pintype "output"))
    )
    (net (code "186") (name "unconnected-(U5-~{CTS}-Pad11)") (class "Default")
      (node (ref "U5") (pin "11") (pinfunction "~{CTS}_11") (pintype "input"))
    )
    (net (code "187") (name "unconnected-(U5-~{DCD}-Pad10)") (class "Default")
      (node (ref "U5") (pin "10") (pinfunction "~{DCD}_10") (pintype "input"))
    )
    (net (code "188") (name "unconnected-(U5-~{DSR}-Pad9)") (class "Default")
      (node (ref "U5") (pin "9") (pinfunction "~{DSR}_9") (pintype "input"))
    )
    (net (code "189") (name "unconnected-(U5-~{DTR}-Pad2)") (class "Default")
      (node (ref "U5") (pin "2") (pinfunction "~{DTR}_2") (pintype "output"))
    )
    (net (code "190") (name "unconnected-(U5-~{RI}-Pad6)") (class "Default")
      (node (ref "U5") (pin "6") (pinfunction "~{RI}_6") (pintype "input"))
    )
    (net (code "191") (name "unconnected-(U5-~{RTS}-Pad3)") (class "Default")
      (node (ref "U5") (pin "3") (pinfunction "~{RTS}_3") (pintype "output"))
    )
    (net (code "192") (name "unconnected-(U10A-IO,_(DQS2L{slash}CQ3L,CDPCLK0)-Pad9)") (class "Default")
      (node (ref "U10") (pin "9") (pinfunction "IO,_(DQS2L/CQ3L,CDPCLK0)_9") (pintype "bidirectional"))
    )
    (net (code "193") (name "unconnected-(U10A-IO,_DIFFIO_L6n-Pad22)") (class "Default")
      (node (ref "U10") (pin "22") (pinfunction "IO,_DIFFIO_L6n_22") (pintype "bidirectional"))
    )
    (net (code "194") (name "unconnected-(U10A-IO,_DIFFIO_L6p,_(DQS0L{slash}CQ1L,DPCLK0)-Pad21)") (class "Default")
      (node (ref "U10") (pin "21") (pinfunction "IO,_DIFFIO_L6p,_(DQS0L/CQ1L,DPCLK0)_21") (pintype "bidirectional"))
    )
    (net (code "195") (name "unconnected-(U10A-IO,_VREFB1N0-Pad13)") (class "Default")
      (node (ref "U10") (pin "13") (pinfunction "IO,_VREFB1N0_13") (pintype "bidirectional"))
    )
    (net (code "196") (name "unconnected-(U10A-IO-Pad18)") (class "Default")
      (node (ref "U10") (pin "18") (pinfunction "IO_18") (pintype "bidirectional"))
    )
    (net (code "197") (name "unconnected-(U10F-IO,_VREFB6N0-Pad169)") (class "Default")
      (node (ref "U10") (pin "169") (pinfunction "IO,_VREFB6N0_169") (pintype "bidirectional"))
    )
    (net (code "198") (name "unconnected-(U10G-IO,_(PADD0),_(DQ5T)-Pad194)") (class "Default")
      (node (ref "U10") (pin "194") (pinfunction "IO,_(PADD0),_(DQ5T)_194") (pintype "bidirectional"))
    )
    (net (code "199") (name "unconnected-(U10G-IO,_DIFFIO_T19n,_(PADD1)-Pad196)") (class "Default")
      (node (ref "U10") (pin "196") (pinfunction "IO,_DIFFIO_T19n,_(PADD1)_196") (pintype "bidirectional"))
    )
    (net (code "200") (name "unconnected-(U10G-IO,_DIFFIO_T23n-Pad182)") (class "Default")
      (node (ref "U10") (pin "182") (pinfunction "IO,_DIFFIO_T23n_182") (pintype "bidirectional"))
    )
    (net (code "201") (name "unconnected-(U10G-IO,_DIFFIO_T23p,_(DQS0T{slash}CQ1T,CDPCLK6)-Pad183)") (class "Default")
      (node (ref "U10") (pin "183") (pinfunction "IO,_DIFFIO_T23p,_(DQS0T/CQ1T,CDPCLK6)_183") (pintype "bidirectional"))
    )
    (net (code "202") (name "unconnected-(U10G-IO,_PLL2_CLKOUTn-Pad185)") (class "Default")
      (node (ref "U10") (pin "185") (pinfunction "IO,_PLL2_CLKOUTn_185") (pintype "bidirectional"))
    )
    (net (code "203") (name "unconnected-(U10G-IO,_PLL2_CLKOUTp-Pad186)") (class "Default")
      (node (ref "U10") (pin "186") (pinfunction "IO,_PLL2_CLKOUTp_186") (pintype "bidirectional"))
    )
    (net (code "204") (name "unconnected-(U10G-IO,_RDN4-Pad188)") (class "Default")
      (node (ref "U10") (pin "188") (pinfunction "IO,_RDN4_188") (pintype "bidirectional"))
    )
    (net (code "205") (name "unconnected-(U10G-IO,_RUP4-Pad187)") (class "Default")
      (node (ref "U10") (pin "187") (pinfunction "IO,_RUP4_187") (pintype "bidirectional"))
    )
    (net (code "206") (name "unconnected-(U10G-IO,_VREFB7N0-Pad195)") (class "Default")
      (node (ref "U10") (pin "195") (pinfunction "IO,_VREFB7N0_195") (pintype "bidirectional"))
    )
    (net (code "207") (name "unconnected-(U10G-IO-Pad181)") (class "Default")
      (node (ref "U10") (pin "181") (pinfunction "IO_181") (pintype "bidirectional"))
    )
    (net (code "208") (name "unconnected-(U10G-IO-Pad184)") (class "Default")
      (node (ref "U10") (pin "184") (pinfunction "IO_184") (pintype "bidirectional"))
    )
    (net (code "209") (name "unconnected-(U10G-IO-Pad189)") (class "Default")
      (node (ref "U10") (pin "189") (pinfunction "IO_189") (pintype "bidirectional"))
    )
  )
)
